# Plytka_AVR.net
KiCad netlist of a schematic drawn in EAGLE
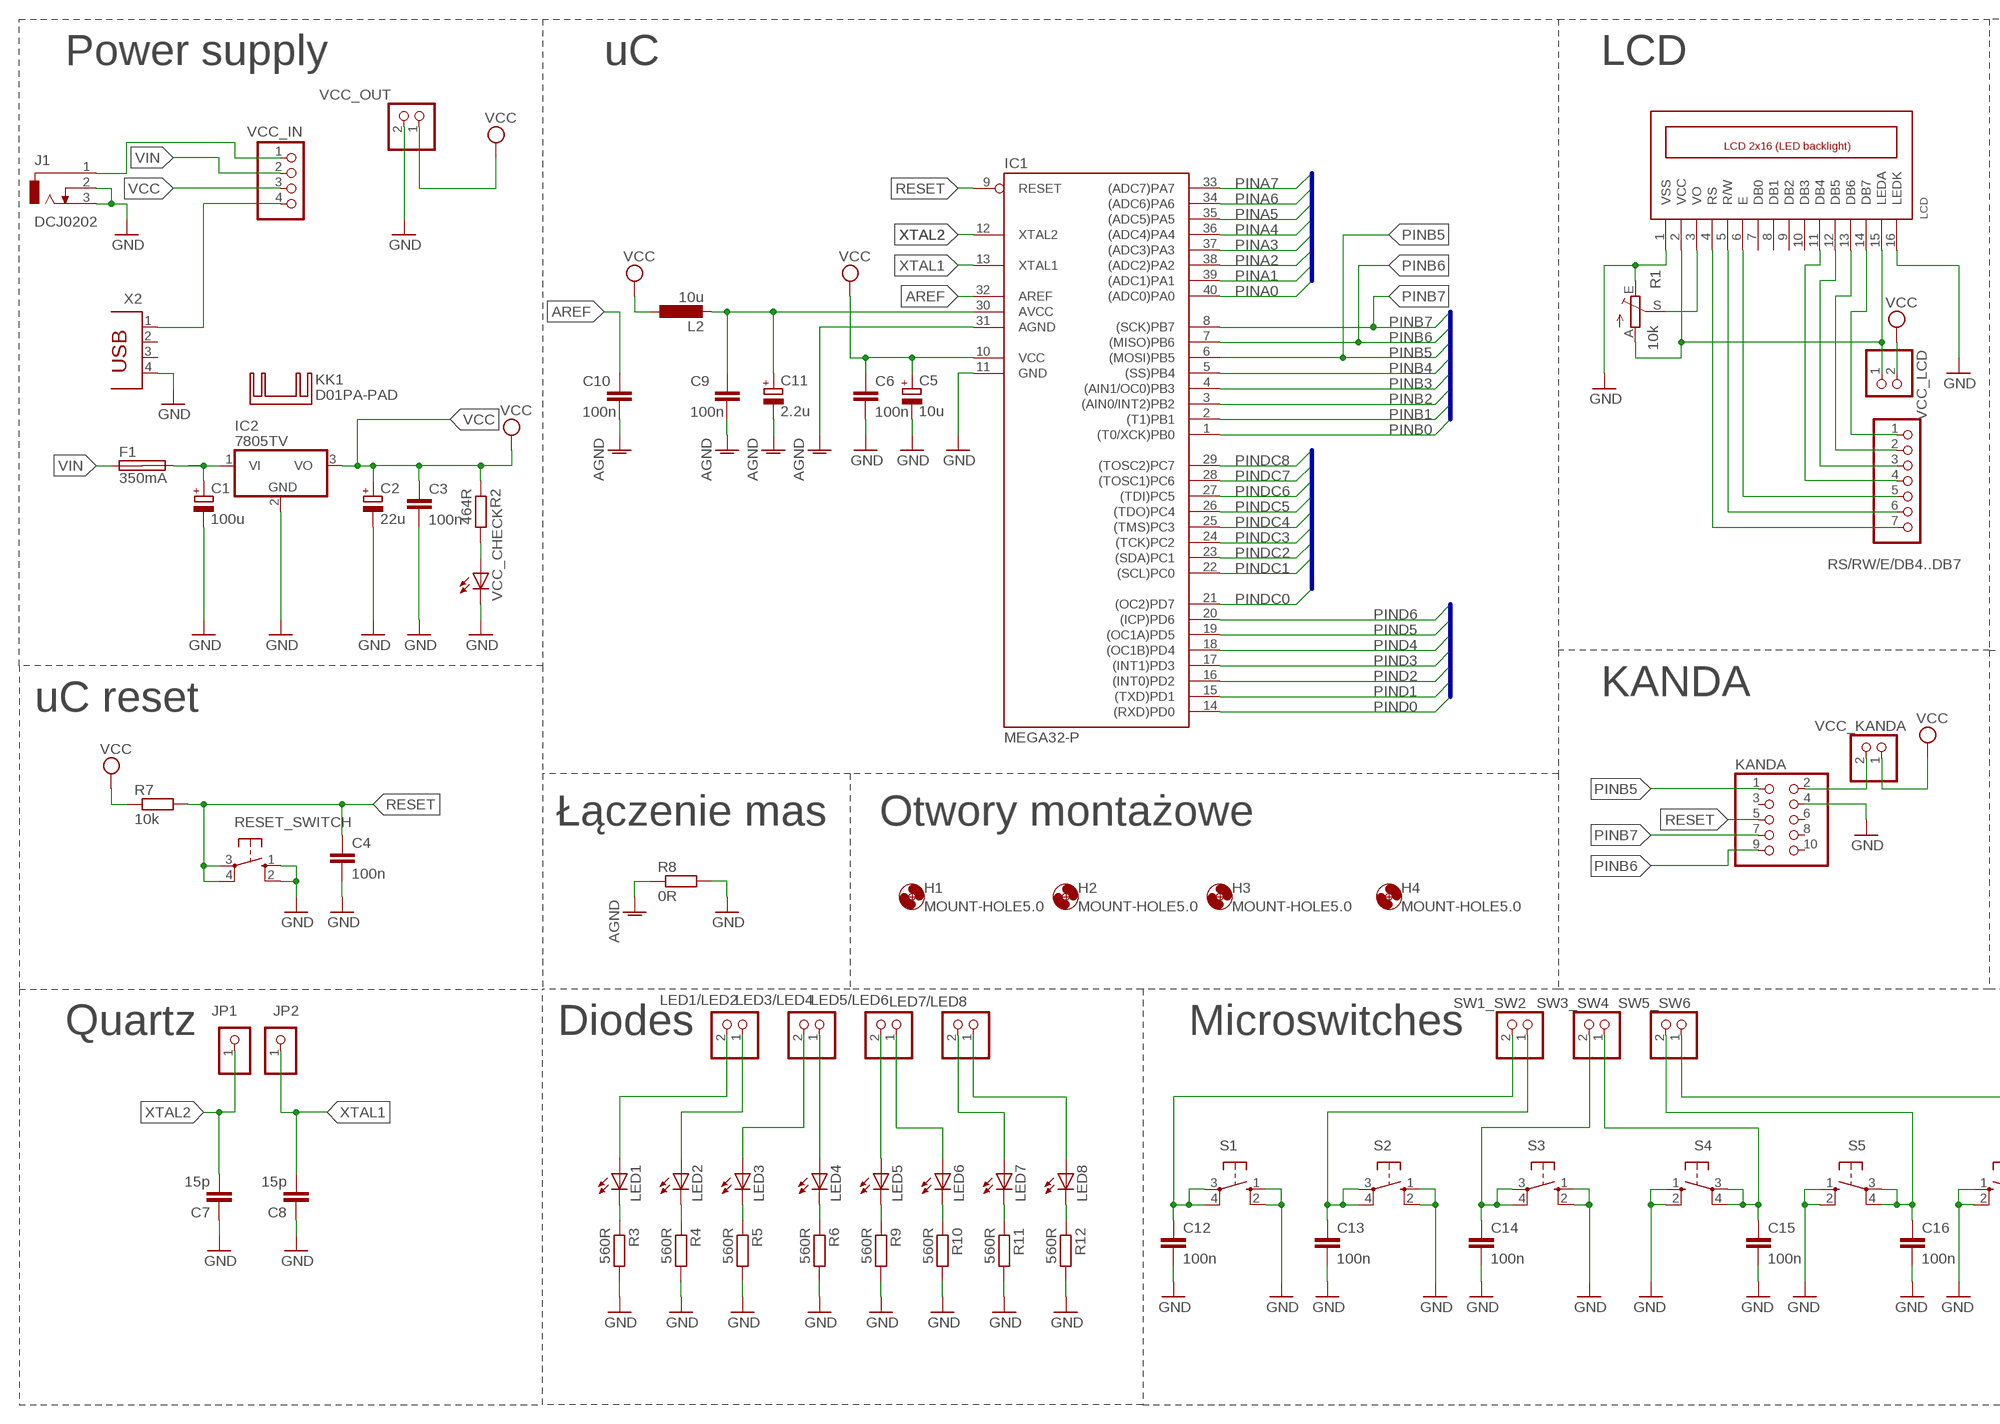
[diagram p0: schematic, sheet 1, part 1 of 2]
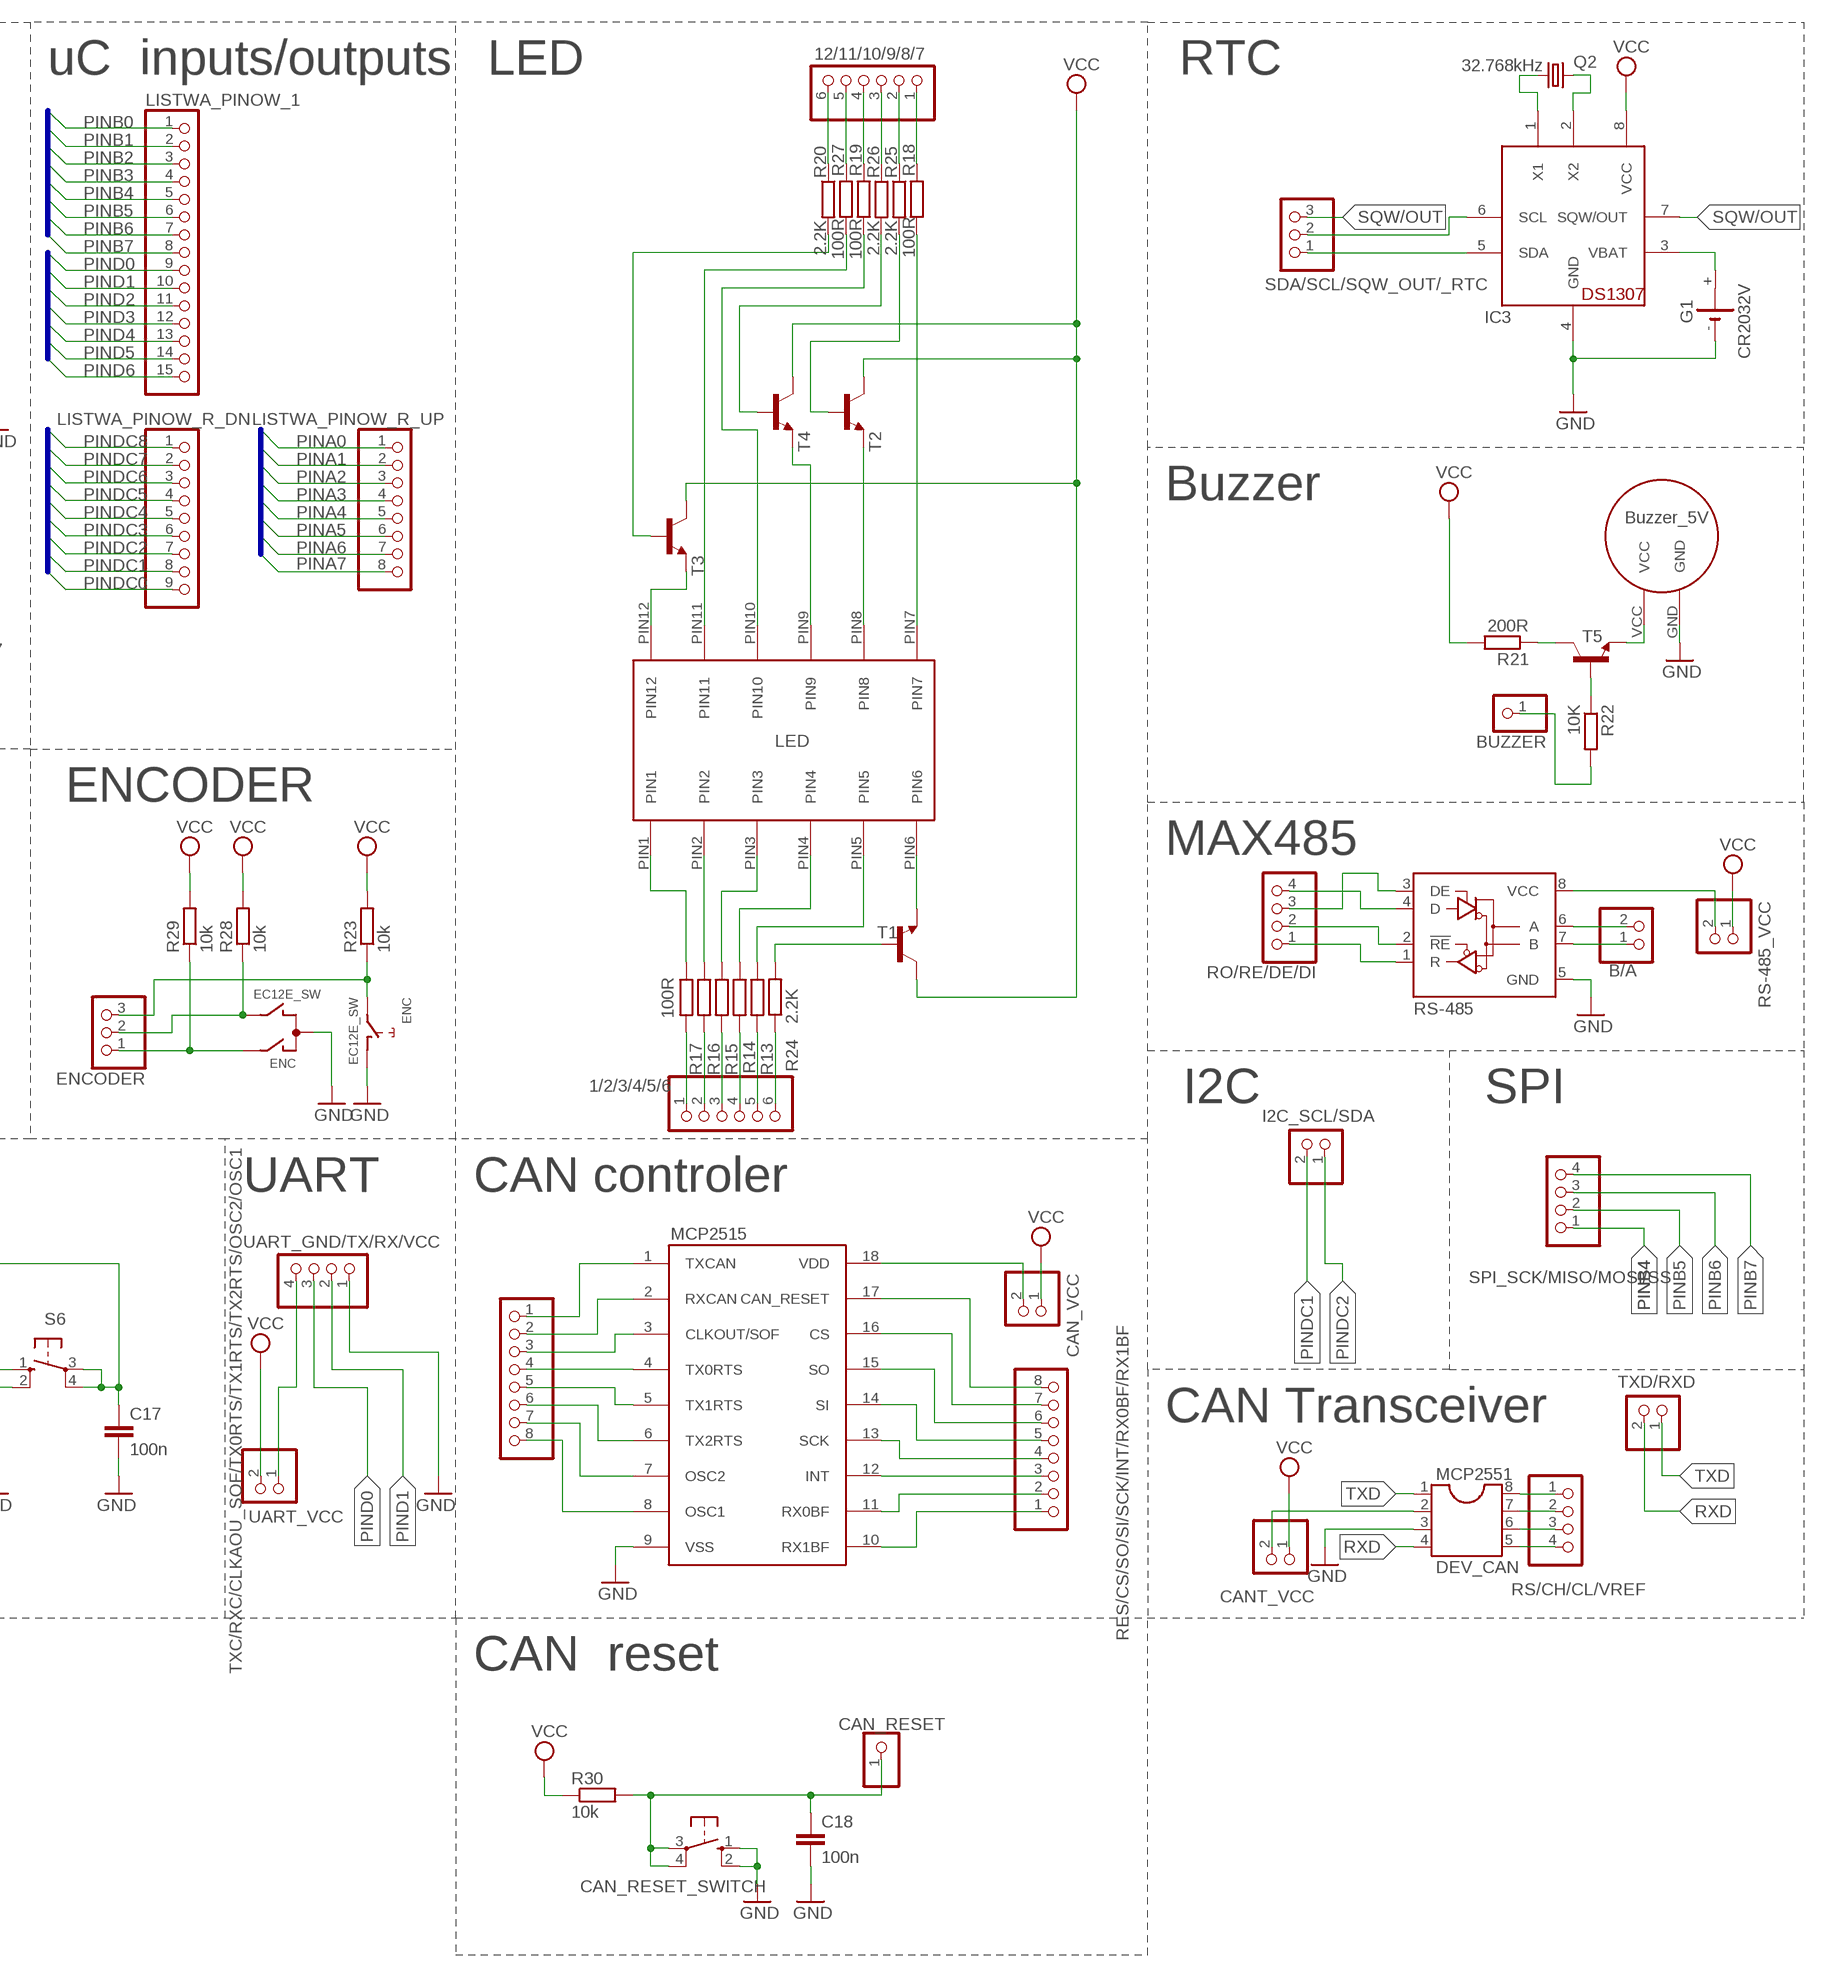
[diagram p1: schematic, sheet 1, part 2 of 2]

(export (version "E")
  (design (tool "Eeschema 10.0.6"))
  (components
    (comp (ref "1/2/3/4/5/6")
      (value "PINHD-1X6")
      (footprint "eagle-import:1X06")
      (libsource (lib "eagle-import") (part "PINHD-1X6"))
    )
    (comp (ref "12/11/10/9/8/7")
      (value "PINHD-1X6")
      (footprint "eagle-import:1X06")
      (libsource (lib "eagle-import") (part "PINHD-1X6"))
    )
    (comp (ref "B/A")
      (value "PINHD-1X2")
      (footprint "eagle-import:1X02")
      (libsource (lib "eagle-import") (part "PINHD-1X2"))
    )
    (comp (ref "BUZZER")
      (value "PINHD-1X1")
      (footprint "eagle-import:1X01")
      (libsource (lib "eagle-import") (part "PINHD-1X1"))
    )
    (comp (ref "C1")
      (value "100u")
      (footprint "eagle-import:E2,5-6")
      (libsource (lib "eagle-import") (part "CPOL-EUE2.5-6"))
    )
    (comp (ref "C2")
      (value "22u")
      (footprint "eagle-import:E2,5-6")
      (libsource (lib "eagle-import") (part "CPOL-EUE2.5-6"))
    )
    (comp (ref "C3")
      (value "100n")
      (footprint "eagle-import:C050-024X044")
      (libsource (lib "eagle-import") (part "C-EU050-024X044"))
    )
    (comp (ref "C4")
      (value "100n")
      (footprint "eagle-import:C050-024X044")
      (libsource (lib "eagle-import") (part "C-EU050-024X044"))
    )
    (comp (ref "C5")
      (value "10u")
      (footprint "eagle-import:E2,5-6")
      (libsource (lib "eagle-import") (part "CPOL-EUE2.5-6"))
    )
    (comp (ref "C6")
      (value "100n")
      (footprint "eagle-import:C050-024X044")
      (libsource (lib "eagle-import") (part "C-EU050-024X044"))
    )
    (comp (ref "C7")
      (value "15p")
      (footprint "eagle-import:C050-024X044")
      (libsource (lib "eagle-import") (part "C-EU050-024X044"))
    )
    (comp (ref "C8")
      (value "15p")
      (footprint "eagle-import:C050-024X044")
      (libsource (lib "eagle-import") (part "C-EU050-024X044"))
    )
    (comp (ref "C9")
      (value "100n")
      (footprint "eagle-import:C050-024X044")
      (libsource (lib "eagle-import") (part "C-EU050-024X044"))
    )
    (comp (ref "C10")
      (value "100n")
      (footprint "eagle-import:C050-024X044")
      (libsource (lib "eagle-import") (part "C-EU050-024X044"))
    )
    (comp (ref "C11")
      (value "2.2u")
      (footprint "eagle-import:E2,5-6")
      (libsource (lib "eagle-import") (part "CPOL-EUE2.5-6"))
    )
    (comp (ref "C12")
      (value "100n")
      (footprint "eagle-import:C050-024X044")
      (libsource (lib "eagle-import") (part "C-EU050-024X044"))
    )
    (comp (ref "C13")
      (value "100n")
      (footprint "eagle-import:C050-024X044")
      (libsource (lib "eagle-import") (part "C-EU050-024X044"))
    )
    (comp (ref "C14")
      (value "100n")
      (footprint "eagle-import:C050-024X044")
      (libsource (lib "eagle-import") (part "C-EU050-024X044"))
    )
    (comp (ref "C15")
      (value "100n")
      (footprint "eagle-import:C050-024X044")
      (libsource (lib "eagle-import") (part "C-EU050-024X044"))
    )
    (comp (ref "C16")
      (value "100n")
      (footprint "eagle-import:C050-024X044")
      (libsource (lib "eagle-import") (part "C-EU050-024X044"))
    )
    (comp (ref "C17")
      (value "100n")
      (footprint "eagle-import:C050-024X044")
      (libsource (lib "eagle-import") (part "C-EU050-024X044"))
    )
    (comp (ref "C18")
      (value "100n")
      (footprint "eagle-import:C050-024X044")
      (libsource (lib "eagle-import") (part "C-EU050-024X044"))
    )
    (comp (ref "CANT_VCC")
      (value "PINHD-1X2")
      (footprint "eagle-import:1X02")
      (libsource (lib "eagle-import") (part "PINHD-1X2"))
    )
    (comp (ref "CAN_RESET")
      (value "PINHD-1X1")
      (footprint "eagle-import:1X01")
      (libsource (lib "eagle-import") (part "PINHD-1X1"))
    )
    (comp (ref "CAN_RESET_SWITCH")
      (value "10-XX")
      (footprint "eagle-import:B3F-10XX")
      (fields (field (name "MPN") "B3F-1000"))
      (libsource (lib "eagle-import") (part "10-XX"))
    )
    (comp (ref "CAN_VCC")
      (value "PINHD-1X2")
      (footprint "eagle-import:1X02")
      (libsource (lib "eagle-import") (part "PINHD-1X2"))
    )
    (comp (ref "ENC")
      (value "EC12E_SW")
      (footprint "eagle-import:ALPS_EC12E_SW")
      (fields (field (name "MPN") "EC12E2424407"))
      (libsource (lib "eagle-import") (part "EC12E_SW"))
    )
    (comp (ref "ENCODER")
      (value "PINHD-1X3")
      (footprint "eagle-import:1X03")
      (libsource (lib "eagle-import") (part "PINHD-1X3"))
    )
    (comp (ref "F1")
      (value "350mA")
      (footprint "eagle-import:SHK20L")
      (libsource (lib "eagle-import") (part "SHK20L"))
    )
    (comp (ref "G1")
      (value "CR2032V")
      (footprint "eagle-import:CR2032V")
      (libsource (lib "eagle-import") (part "CR2032V"))
    )
    (comp (ref "H1")
      (value "MOUNT-HOLE5.0")
      (footprint "eagle-import:5,0")
      (libsource (lib "eagle-import") (part "MOUNT-HOLE5.0"))
    )
    (comp (ref "H2")
      (value "MOUNT-HOLE5.0")
      (footprint "eagle-import:5,0")
      (libsource (lib "eagle-import") (part "MOUNT-HOLE5.0"))
    )
    (comp (ref "H3")
      (value "MOUNT-HOLE5.0")
      (footprint "eagle-import:5,0")
      (libsource (lib "eagle-import") (part "MOUNT-HOLE5.0"))
    )
    (comp (ref "H4")
      (value "MOUNT-HOLE5.0")
      (footprint "eagle-import:5,0")
      (libsource (lib "eagle-import") (part "MOUNT-HOLE5.0"))
    )
    (comp (ref "I2C_SCL/SDA")
      (value "PINHD-1X2")
      (footprint "eagle-import:1X02")
      (libsource (lib "eagle-import") (part "PINHD-1X2"))
    )
    (comp (ref "IC1")
      (value "MEGA32-P")
      (footprint "eagle-import:DIL40")
      (fields (field (name "MPN") "ATMEGA32-16PU"))
      (libsource (lib "eagle-import") (part "MEGA32-P"))
    )
    (comp (ref "IC2")
      (value "7805TV")
      (footprint "eagle-import:TO220V")
      (libsource (lib "eagle-import") (part "78TV05"))
    )
    (comp (ref "IC3")
      (value "DS1307")
      (footprint "eagle-import:DIL08")
      (libsource (lib "eagle-import") (part "DS1307"))
    )
    (comp (ref "J1")
      (value "DCJ0202")
      (footprint "eagle-import:DCJ0202")
      (libsource (lib "eagle-import") (part "DCJ0202"))
    )
    (comp (ref "JP1")
      (value "PINHD-1X1")
      (footprint "eagle-import:1X01")
      (libsource (lib "eagle-import") (part "PINHD-1X1"))
    )
    (comp (ref "JP2")
      (value "PINHD-1X1")
      (footprint "eagle-import:1X01")
      (libsource (lib "eagle-import") (part "PINHD-1X1"))
    )
    (comp (ref "KANDA")
      (value "PINHD-2X5")
      (footprint "eagle-import:2X05")
      (libsource (lib "eagle-import") (part "PINHD-2X5"))
    )
    (comp (ref "KK1")
      (value "D01PA-PAD")
      (footprint "eagle-import:D01PA-PAD")
      (libsource (lib "eagle-import") (part "D01PA-PAD"))
    )
    (comp (ref "L2")
      (value "10u")
      (footprint "eagle-import:0204_7")
      (libsource (lib "eagle-import") (part "L-EU0204/7"))
    )
    (comp (ref "LCD")
      (value "LCD_2X16_SIL")
      (footprint "eagle-import:HY-1602F")
      (libsource (lib "eagle-import") (part "LCD_2X16_SIL"))
    )
    (comp (ref "LED1")
      (value "LED5MM")
      (footprint "eagle-import:LED5MM")
      (libsource (lib "eagle-import") (part "LED5MM"))
    )
    (comp (ref "LED1/LED2")
      (value "PINHD-1X2")
      (footprint "eagle-import:1X02")
      (libsource (lib "eagle-import") (part "PINHD-1X2"))
    )
    (comp (ref "LED2")
      (value "LED5MM")
      (footprint "eagle-import:LED5MM")
      (libsource (lib "eagle-import") (part "LED5MM"))
    )
    (comp (ref "LED3")
      (value "LED5MM")
      (footprint "eagle-import:LED5MM")
      (libsource (lib "eagle-import") (part "LED5MM"))
    )
    (comp (ref "LED3/LED4")
      (value "PINHD-1X2")
      (footprint "eagle-import:1X02")
      (libsource (lib "eagle-import") (part "PINHD-1X2"))
    )
    (comp (ref "LED4")
      (value "LED5MM")
      (footprint "eagle-import:LED5MM")
      (libsource (lib "eagle-import") (part "LED5MM"))
    )
    (comp (ref "LED5")
      (value "LED5MM")
      (footprint "eagle-import:LED5MM")
      (libsource (lib "eagle-import") (part "LED5MM"))
    )
    (comp (ref "LED5/LED6")
      (value "PINHD-1X2")
      (footprint "eagle-import:1X02")
      (libsource (lib "eagle-import") (part "PINHD-1X2"))
    )
    (comp (ref "LED6")
      (value "LED5MM")
      (footprint "eagle-import:LED5MM")
      (libsource (lib "eagle-import") (part "LED5MM"))
    )
    (comp (ref "LED7")
      (value "LED5MM")
      (footprint "eagle-import:LED5MM")
      (libsource (lib "eagle-import") (part "LED5MM"))
    )
    (comp (ref "LED7/LED8")
      (value "PINHD-1X2")
      (footprint "eagle-import:1X02")
      (libsource (lib "eagle-import") (part "PINHD-1X2"))
    )
    (comp (ref "LED8")
      (value "LED5MM")
      (footprint "eagle-import:LED5MM")
      (libsource (lib "eagle-import") (part "LED5MM"))
    )
    (comp (ref "LISTWA_PINOW_1")
      (value "PINHD-1X15")
      (footprint "eagle-import:1X15")
      (libsource (lib "eagle-import") (part "PINHD-1X15"))
    )
    (comp (ref "LISTWA_PINOW_R_DN")
      (value "PINHD-1X9")
      (footprint "eagle-import:1X09")
      (libsource (lib "eagle-import") (part "PINHD-1X9"))
    )
    (comp (ref "LISTWA_PINOW_R_UP")
      (value "PINHD-1X8MAT8")
      (footprint "eagle-import:1X08")
      (libsource (lib "eagle-import") (part "PINHD-1X8MAT8"))
    )
    (comp (ref "MCP2551")
      (value "DEV_CAN")
      (footprint "eagle-import:DIL08")
      (libsource (lib "eagle-import") (part "DEV_CAN"))
    )
    (comp (ref "Q2")
      (value "32.768kHz")
      (footprint "eagle-import:TC26V")
      (libsource (lib "eagle-import") (part "CRYSTALTC26V"))
    )
    (comp (ref "R1")
      (value "10k")
      (footprint "eagle-import:CA6V")
      (libsource (lib "eagle-import") (part "TRIM_EU-CA6V"))
    )
    (comp (ref "R2")
      (value "464R")
      (footprint "eagle-import:0204_7")
      (libsource (lib "eagle-import") (part "R-EU_0204/7"))
    )
    (comp (ref "R3")
      (value "560R")
      (footprint "eagle-import:0204_7")
      (libsource (lib "eagle-import") (part "R-EU_0204/7"))
    )
    (comp (ref "R4")
      (value "560R")
      (footprint "eagle-import:0204_7")
      (libsource (lib "eagle-import") (part "R-EU_0204/7"))
    )
    (comp (ref "R5")
      (value "560R")
      (footprint "eagle-import:0204_7")
      (libsource (lib "eagle-import") (part "R-EU_0204/7"))
    )
    (comp (ref "R6")
      (value "560R")
      (footprint "eagle-import:0204_7")
      (libsource (lib "eagle-import") (part "R-EU_0204/7"))
    )
    (comp (ref "R7")
      (value "10k")
      (footprint "eagle-import:0204_7")
      (libsource (lib "eagle-import") (part "R-EU_0204/7"))
    )
    (comp (ref "R8")
      (value "0R")
      (footprint "eagle-import:0204_7")
      (libsource (lib "eagle-import") (part "R-EU_0204/7"))
    )
    (comp (ref "R9")
      (value "560R")
      (footprint "eagle-import:0204_7")
      (libsource (lib "eagle-import") (part "R-EU_0204/7"))
    )
    (comp (ref "R10")
      (value "560R")
      (footprint "eagle-import:0204_7")
      (libsource (lib "eagle-import") (part "R-EU_0204/7"))
    )
    (comp (ref "R11")
      (value "560R")
      (footprint "eagle-import:0204_7")
      (libsource (lib "eagle-import") (part "R-EU_0204/7"))
    )
    (comp (ref "R12")
      (value "560R")
      (footprint "eagle-import:0204_7")
      (libsource (lib "eagle-import") (part "R-EU_0204/7"))
    )
    (comp (ref "R13")
      (value "100R")
      (footprint "eagle-import:0204_7")
      (libsource (lib "eagle-import") (part "R-EU_0204/7"))
    )
    (comp (ref "R14")
      (value "100R")
      (footprint "eagle-import:0204_7")
      (libsource (lib "eagle-import") (part "R-EU_0204/7"))
    )
    (comp (ref "R15")
      (value "100R")
      (footprint "eagle-import:0204_7")
      (libsource (lib "eagle-import") (part "R-EU_0204/7"))
    )
    (comp (ref "R16")
      (value "100R")
      (footprint "eagle-import:0204_7")
      (libsource (lib "eagle-import") (part "R-EU_0204/7"))
    )
    (comp (ref "R17")
      (value "100R")
      (footprint "eagle-import:0204_7")
      (libsource (lib "eagle-import") (part "R-EU_0204/7"))
    )
    (comp (ref "R18")
      (value "100R")
      (footprint "eagle-import:0204_7")
      (libsource (lib "eagle-import") (part "R-EU_0204/7"))
    )
    (comp (ref "R19")
      (value "100R")
      (footprint "eagle-import:0204_7")
      (libsource (lib "eagle-import") (part "R-EU_0204/7"))
    )
    (comp (ref "R20")
      (value "2.2K")
      (footprint "eagle-import:0204_7")
      (libsource (lib "eagle-import") (part "R-EU_0204/7"))
    )
    (comp (ref "R21")
      (value "200R")
      (footprint "eagle-import:0204_7")
      (libsource (lib "eagle-import") (part "R-EU_0204/7"))
    )
    (comp (ref "R22")
      (value "10K")
      (footprint "eagle-import:0204_7")
      (libsource (lib "eagle-import") (part "R-EU_0204/7"))
    )
    (comp (ref "R23")
      (value "10k")
      (footprint "eagle-import:0204_7")
      (libsource (lib "eagle-import") (part "R-EU_0204/7"))
    )
    (comp (ref "R24")
      (value "2.2K")
      (footprint "eagle-import:0204_7")
      (libsource (lib "eagle-import") (part "R-EU_0204/7"))
    )
    (comp (ref "R25")
      (value "2.2K")
      (footprint "eagle-import:0204_7")
      (libsource (lib "eagle-import") (part "R-EU_0204/7"))
    )
    (comp (ref "R26")
      (value "2.2K")
      (footprint "eagle-import:0204_7")
      (libsource (lib "eagle-import") (part "R-EU_0204/7"))
    )
    (comp (ref "R27")
      (value "100R")
      (footprint "eagle-import:0204_7")
      (libsource (lib "eagle-import") (part "R-EU_0204/7"))
    )
    (comp (ref "R28")
      (value "10k")
      (footprint "eagle-import:0204_7")
      (libsource (lib "eagle-import") (part "R-EU_0204/7"))
    )
    (comp (ref "R29")
      (value "10k")
      (footprint "eagle-import:0204_7")
      (libsource (lib "eagle-import") (part "R-EU_0204/7"))
    )
    (comp (ref "R30")
      (value "10k")
      (footprint "eagle-import:0204_7")
      (libsource (lib "eagle-import") (part "R-EU_0204/7"))
    )
    (comp (ref "RES/CS/SO/SI/SCK/INT/RX0BF/RX1BF")
      (value "PINHD-1X8")
      (footprint "eagle-import:1X08")
      (libsource (lib "eagle-import") (part "PINHD-1X8"))
    )
    (comp (ref "RESET_SWITCH")
      (value "10-XX")
      (footprint "eagle-import:B3F-10XX")
      (fields (field (name "MPN") "B3F-1000"))
      (libsource (lib "eagle-import") (part "10-XX"))
    )
    (comp (ref "RO/RE/DE/DI")
      (value "PINHD-1X4")
      (footprint "eagle-import:1X04")
      (libsource (lib "eagle-import") (part "PINHD-1X4"))
    )
    (comp (ref "RS-485")
      (value "RS-485")
      (footprint "eagle-import:DIL08")
      (libsource (lib "eagle-import") (part "75176AP"))
    )
    (comp (ref "RS-485_VCC")
      (value "PINHD-1X2")
      (footprint "eagle-import:1X02")
      (libsource (lib "eagle-import") (part "PINHD-1X2"))
    )
    (comp (ref "RS/CH/CL/VREF")
      (value "PINHD-1X4")
      (footprint "eagle-import:1X04")
      (libsource (lib "eagle-import") (part "PINHD-1X4"))
    )
    (comp (ref "RS/RW/E/DB4..DB7")
      (value "PINHD-1X7MAT_LCD")
      (footprint "eagle-import:1X07")
      (libsource (lib "eagle-import") (part "PINHD-1X7MAT_LCD"))
    )
    (comp (ref "S1")
      (value "10-XX")
      (footprint "eagle-import:B3F-10XX")
      (fields (field (name "MPN") "B3F-1000"))
      (libsource (lib "eagle-import") (part "10-XX"))
    )
    (comp (ref "S2")
      (value "10-XX")
      (footprint "eagle-import:B3F-10XX")
      (fields (field (name "MPN") "B3F-1000"))
      (libsource (lib "eagle-import") (part "10-XX"))
    )
    (comp (ref "S3")
      (value "10-XX")
      (footprint "eagle-import:B3F-10XX")
      (fields (field (name "MPN") "B3F-1000"))
      (libsource (lib "eagle-import") (part "10-XX"))
    )
    (comp (ref "S4")
      (value "10-XX")
      (footprint "eagle-import:B3F-10XX")
      (fields (field (name "MPN") "B3F-1000"))
      (libsource (lib "eagle-import") (part "10-XX"))
    )
    (comp (ref "S5")
      (value "10-XX")
      (footprint "eagle-import:B3F-10XX")
      (fields (field (name "MPN") "B3F-1000"))
      (libsource (lib "eagle-import") (part "10-XX"))
    )
    (comp (ref "S6")
      (value "10-XX")
      (footprint "eagle-import:B3F-10XX")
      (fields (field (name "MPN") "B3F-1000"))
      (libsource (lib "eagle-import") (part "10-XX"))
    )
    (comp (ref "SDA/SCL/SQW_OUT/_RTC")
      (value "PINHD-1X3")
      (footprint "eagle-import:1X03")
      (libsource (lib "eagle-import") (part "PINHD-1X3"))
    )
    (comp (ref "SPI_SCK/MISO/MOSI/SS")
      (value "PINHD-1X4")
      (footprint "eagle-import:1X04")
      (libsource (lib "eagle-import") (part "PINHD-1X4"))
    )
    (comp (ref "SW1_SW2")
      (value "PINHD-1X2")
      (footprint "eagle-import:1X02")
      (libsource (lib "eagle-import") (part "PINHD-1X2"))
    )
    (comp (ref "SW3_SW4")
      (value "PINHD-1X2")
      (footprint "eagle-import:1X02")
      (libsource (lib "eagle-import") (part "PINHD-1X2"))
    )
    (comp (ref "SW5_SW6")
      (value "PINHD-1X2")
      (footprint "eagle-import:1X02")
      (libsource (lib "eagle-import") (part "PINHD-1X2"))
    )
    (comp (ref "T1")
      (value "-NPN-TO92")
      (footprint "eagle-import:TO92")
      (libsource (lib "eagle-import") (part "-NPN-TO92"))
    )
    (comp (ref "T2")
      (value "-NPN-TO92")
      (footprint "eagle-import:TO92")
      (libsource (lib "eagle-import") (part "-NPN-TO92"))
    )
    (comp (ref "T3")
      (value "-NPN-TO92")
      (footprint "eagle-import:TO92")
      (libsource (lib "eagle-import") (part "-NPN-TO92"))
    )
    (comp (ref "T4")
      (value "-NPN-TO92")
      (footprint "eagle-import:TO92")
      (libsource (lib "eagle-import") (part "-NPN-TO92"))
    )
    (comp (ref "T5")
      (value "-NPN-TO92")
      (footprint "eagle-import:TO92")
      (libsource (lib "eagle-import") (part "-NPN-TO92"))
    )
    (comp (ref "TXC/RXC/CLKAOU_SOF/TX0RTS/TX1RTS/TX2RTS/OSC2/OSC1")
      (value "PINHD-1X8")
      (footprint "eagle-import:1X08")
      (libsource (lib "eagle-import") (part "PINHD-1X8"))
    )
    (comp (ref "TXD/RXD")
      (value "PINHD-1X2")
      (footprint "eagle-import:1X02")
      (libsource (lib "eagle-import") (part "PINHD-1X2"))
    )
    (comp (ref "U$1")
      (value "LED_MAT")
      (footprint "eagle-import:LED_MOJ")
      (libsource (lib "eagle-import") (part "LED_MAT"))
    )
    (comp (ref "U$2")
      (value "BUZZER_MAT")
      (footprint "eagle-import:BUZZER_MAT")
      (libsource (lib "eagle-import") (part "BUZZER_MAT"))
    )
    (comp (ref "U$3")
      (value "MCP2515")
      (footprint "eagle-import:DIP18")
      (libsource (lib "eagle-import") (part "MCP2515"))
    )
    (comp (ref "UART_GND/TX/RX/VCC")
      (value "PINHD-1X4")
      (footprint "eagle-import:1X04")
      (libsource (lib "eagle-import") (part "PINHD-1X4"))
    )
    (comp (ref "UART_VCC")
      (value "PINHD-1X2")
      (footprint "eagle-import:1X02")
      (libsource (lib "eagle-import") (part "PINHD-1X2"))
    )
    (comp (ref "VCC_CHECK")
      (value "LED5MM")
      (footprint "eagle-import:LED5MM")
      (libsource (lib "eagle-import") (part "LED5MM"))
    )
    (comp (ref "VCC_IN")
      (value "PINHD-1X4")
      (footprint "eagle-import:1X04")
      (libsource (lib "eagle-import") (part "PINHD-1X4"))
    )
    (comp (ref "VCC_KANDA")
      (value "PINHD-1X2")
      (footprint "eagle-import:1X02")
      (libsource (lib "eagle-import") (part "PINHD-1X2"))
    )
    (comp (ref "VCC_LCD")
      (value "PINHD-1X2")
      (footprint "eagle-import:1X02")
      (libsource (lib "eagle-import") (part "PINHD-1X2"))
    )
    (comp (ref "VCC_OUT")
      (value "PINHD-1X2")
      (footprint "eagle-import:1X02")
      (libsource (lib "eagle-import") (part "PINHD-1X2"))
    )
    (comp (ref "X2")
      (value "PN87520")
      (footprint "eagle-import:PN87520")
      (libsource (lib "eagle-import") (part "PN87520"))
    )
  )
  (nets
    (net (code "1") (name "/PINA0") (class "Default")
      (node (ref "IC1") (pin "40") (pinfunction "(ADC0)PA0_40") (pintype "bidirectional"))
      (node (ref "LISTWA_PINOW_R_UP") (pin "1") (pinfunction "1_1") (pintype "passive"))
    )
    (net (code "2") (name "/PINA1") (class "Default")
      (node (ref "IC1") (pin "39") (pinfunction "(ADC1)PA1_39") (pintype "bidirectional"))
      (node (ref "LISTWA_PINOW_R_UP") (pin "2") (pinfunction "2_2") (pintype "passive"))
    )
    (net (code "3") (name "/PINA2") (class "Default")
      (node (ref "IC1") (pin "38") (pinfunction "(ADC2)PA2_38") (pintype "bidirectional"))
      (node (ref "LISTWA_PINOW_R_UP") (pin "3") (pinfunction "3_3") (pintype "passive"))
    )
    (net (code "4") (name "/PINA3") (class "Default")
      (node (ref "IC1") (pin "37") (pinfunction "(ADC3)PA3_37") (pintype "bidirectional"))
      (node (ref "LISTWA_PINOW_R_UP") (pin "4") (pinfunction "4_4") (pintype "passive"))
    )
    (net (code "5") (name "/PINA4") (class "Default")
      (node (ref "IC1") (pin "36") (pinfunction "(ADC4)PA4_36") (pintype "bidirectional"))
      (node (ref "LISTWA_PINOW_R_UP") (pin "5") (pinfunction "5_5") (pintype "passive"))
    )
    (net (code "6") (name "/PINA5") (class "Default")
      (node (ref "IC1") (pin "35") (pinfunction "(ADC5)PA5_35") (pintype "bidirectional"))
      (node (ref "LISTWA_PINOW_R_UP") (pin "6") (pinfunction "6_6") (pintype "passive"))
    )
    (net (code "7") (name "/PINA6") (class "Default")
      (node (ref "IC1") (pin "34") (pinfunction "(ADC6)PA6_34") (pintype "bidirectional"))
      (node (ref "LISTWA_PINOW_R_UP") (pin "7") (pinfunction "7_7") (pintype "passive"))
    )
    (net (code "8") (name "/PINA7") (class "Default")
      (node (ref "IC1") (pin "33") (pinfunction "(ADC7)PA7_33") (pintype "bidirectional"))
      (node (ref "LISTWA_PINOW_R_UP") (pin "8") (pinfunction "8_8") (pintype "passive"))
    )
    (net (code "9") (name "/PINB0") (class "Default")
      (node (ref "IC1") (pin "1") (pinfunction "(T0/XCK)PB0_1") (pintype "bidirectional"))
      (node (ref "LISTWA_PINOW_1") (pin "1") (pinfunction "1_1") (pintype "passive"))
    )
    (net (code "10") (name "/PINB1") (class "Default")
      (node (ref "IC1") (pin "2") (pinfunction "(T1)PB1_2") (pintype "bidirectional"))
      (node (ref "LISTWA_PINOW_1") (pin "2") (pinfunction "2_2") (pintype "passive"))
    )
    (net (code "11") (name "/PINB2") (class "Default")
      (node (ref "IC1") (pin "3") (pinfunction "(AIN0/INT2)PB2_3") (pintype "bidirectional"))
      (node (ref "LISTWA_PINOW_1") (pin "3") (pinfunction "3_3") (pintype "passive"))
    )
    (net (code "12") (name "/PINB3") (class "Default")
      (node (ref "IC1") (pin "4") (pinfunction "(AIN1/OC0)PB3_4") (pintype "bidirectional"))
      (node (ref "LISTWA_PINOW_1") (pin "4") (pinfunction "4_4") (pintype "passive"))
    )
    (net (code "13") (name "/PIND2") (class "Default")
      (node (ref "IC1") (pin "16") (pinfunction "(INT0)PD2_16") (pintype "bidirectional"))
      (node (ref "LISTWA_PINOW_1") (pin "11") (pinfunction "11_11") (pintype "passive"))
    )
    (net (code "14") (name "/PIND3") (class "Default")
      (node (ref "IC1") (pin "17") (pinfunction "(INT1)PD3_17") (pintype "bidirectional"))
      (node (ref "LISTWA_PINOW_1") (pin "12") (pinfunction "12_12") (pintype "passive"))
    )
    (net (code "15") (name "/PIND4") (class "Default")
      (node (ref "IC1") (pin "18") (pinfunction "(OC1B)PD4_18") (pintype "bidirectional"))
      (node (ref "LISTWA_PINOW_1") (pin "13") (pinfunction "13_13") (pintype "passive"))
    )
    (net (code "16") (name "/PIND5") (class "Default")
      (node (ref "IC1") (pin "19") (pinfunction "(OC1A)PD5_19") (pintype "bidirectional"))
      (node (ref "LISTWA_PINOW_1") (pin "14") (pinfunction "14_14") (pintype "passive"))
    )
    (net (code "17") (name "/PIND6") (class "Default")
      (node (ref "IC1") (pin "20") (pinfunction "(ICP)PD6_20") (pintype "bidirectional"))
      (node (ref "LISTWA_PINOW_1") (pin "15") (pinfunction "15_15") (pintype "passive"))
    )
    (net (code "18") (name "/PINDC0") (class "Default")
      (node (ref "IC1") (pin "21") (pinfunction "(OC2)PD7_21") (pintype "bidirectional"))
      (node (ref "LISTWA_PINOW_R_DN") (pin "9") (pinfunction "9_9") (pintype "passive"))
    )
    (net (code "19") (name "/PINDC3") (class "Default")
      (node (ref "IC1") (pin "24") (pinfunction "(TCK)PC2_24") (pintype "bidirectional"))
      (node (ref "LISTWA_PINOW_R_DN") (pin "6") (pinfunction "6_6") (pintype "passive"))
    )
    (net (code "20") (name "/PINDC4") (class "Default")
      (node (ref "IC1") (pin "25") (pinfunction "(TMS)PC3_25") (pintype "bidirectional"))
      (node (ref "LISTWA_PINOW_R_DN") (pin "5") (pinfunction "5_5") (pintype "passive"))
    )
    (net (code "21") (name "/PINDC5") (class "Default")
      (node (ref "IC1") (pin "26") (pinfunction "(TDO)PC4_26") (pintype "bidirectional"))
      (node (ref "LISTWA_PINOW_R_DN") (pin "4") (pinfunction "4_4") (pintype "passive"))
    )
    (net (code "22") (name "/PINDC6") (class "Default")
      (node (ref "IC1") (pin "27") (pinfunction "(TDI)PC5_27") (pintype "bidirectional"))
      (node (ref "LISTWA_PINOW_R_DN") (pin "3") (pinfunction "3_3") (pintype "passive"))
    )
    (net (code "23") (name "/PINDC7") (class "Default")
      (node (ref "IC1") (pin "28") (pinfunction "(TOSC1)PC6_28") (pintype "bidirectional"))
      (node (ref "LISTWA_PINOW_R_DN") (pin "2") (pinfunction "2_2") (pintype "passive"))
    )
    (net (code "24") (name "/PINDC8") (class "Default")
      (node (ref "IC1") (pin "29") (pinfunction "(TOSC2)PC7_29") (pintype "bidirectional"))
      (node (ref "LISTWA_PINOW_R_DN") (pin "1") (pinfunction "1_1") (pintype "passive"))
    )
    (net (code "25") (name "AGND") (class "Default")
      (node (ref "C10") (pin "2") (pinfunction "2_2") (pintype "passive"))
      (node (ref "C11") (pin "-") (pinfunction "-_-") (pintype "passive"))
      (node (ref "C9") (pin "2") (pinfunction "2_2") (pintype "passive"))
      (node (ref "IC1") (pin "31") (pinfunction "AGND_31") (pintype "power_in"))
      (node (ref "R8") (pin "1") (pinfunction "1_1") (pintype "passive"))
    )
    (net (code "26") (name "AREF") (class "Default")
      (node (ref "C10") (pin "1") (pinfunction "1_1") (pintype "passive"))
      (node (ref "IC1") (pin "32") (pinfunction "AREF_32") (pintype "passive"))
    )
    (net (code "27") (name "GND") (class "Default")
      (node (ref "C1") (pin "-") (pinfunction "-_-") (pintype "passive"))
      (node (ref "C12") (pin "2") (pinfunction "2_2") (pintype "passive"))
      (node (ref "C13") (pin "2") (pinfunction "2_2") (pintype "passive"))
      (node (ref "C14") (pin "2") (pinfunction "2_2") (pintype "passive"))
      (node (ref "C15") (pin "2") (pinfunction "2_2") (pintype "passive"))
      (node (ref "C16") (pin "2") (pinfunction "2_2") (pintype "passive"))
      (node (ref "C17") (pin "2") (pinfunction "2_2") (pintype "passive"))
      (node (ref "C18") (pin "2") (pinfunction "2_2") (pintype "passive"))
      (node (ref "C2") (pin "-") (pinfunction "-_-") (pintype "passive"))
      (node (ref "C3") (pin "2") (pinfunction "2_2") (pintype "passive"))
      (node (ref "C4") (pin "2") (pinfunction "2_2") (pintype "passive"))
      (node (ref "C5") (pin "-") (pinfunction "-_-") (pintype "passive"))
      (node (ref "C6") (pin "2") (pinfunction "2_2") (pintype "passive"))
      (node (ref "C7") (pin "1") (pinfunction "1_1") (pintype "passive"))
      (node (ref "C8") (pin "1") (pinfunction "1_1") (pintype "passive"))
      (node (ref "CAN_RESET_SWITCH") (pin "1") (pinfunction "S_1") (pintype "passive"))
      (node (ref "CAN_RESET_SWITCH") (pin "2") (pinfunction "S1_2") (pintype "passive"))
      (node (ref "ENC") (pin "C") (pinfunction "C_C") (pintype "passive"))
      (node (ref "ENC") (pin "D") (pinfunction "1_D") (pintype "passive"))
      (node (ref "G1") (pin "-") (pinfunction "-_-") (pintype "passive"))
      (node (ref "IC1") (pin "11") (pinfunction "GND_11") (pintype "power_in"))
      (node (ref "IC2") (pin "2") (pinfunction "GND_2") (pintype "passive"))
      (node (ref "IC3") (pin "4") (pinfunction "GND_4") (pintype "power_in"))
      (node (ref "J1") (pin "2") (pinfunction "2_2") (pintype "passive"))
      (node (ref "J1") (pin "3") (pinfunction "3_3") (pintype "passive"))
      (node (ref "KANDA") (pin "4") (pinfunction "4_4") (pintype "passive"))
      (node (ref "LCD") (pin "1") (pinfunction "VSS_1") (pintype "power_in"))
      (node (ref "LCD") (pin "16") (pinfunction "LEDK_16") (pintype "passive"))
      (node (ref "MCP2551") (pin "3") (pinfunction "VDD_3") (pintype "passive"))
      (node (ref "R1") (pin "E") (pinfunction "E_E") (pintype "passive"))
      (node (ref "R10") (pin "2") (pinfunction "2_2") (pintype "passive"))
      (node (ref "R11") (pin "2") (pinfunction "2_2") (pintype "passive"))
      (node (ref "R12") (pin "2") (pinfunction "2_2") (pintype "passive"))
      (node (ref "R3") (pin "2") (pinfunction "2_2") (pintype "passive"))
      (node (ref "R4") (pin "2") (pinfunction "2_2") (pintype "passive"))
      (node (ref "R5") (pin "2") (pinfunction "2_2") (pintype "passive"))
      (node (ref "R6") (pin "2") (pinfunction "2_2") (pintype "passive"))
      (node (ref "R8") (pin "2") (pinfunction "2_2") (pintype "passive"))
      (node (ref "R9") (pin "2") (pinfunction "2_2") (pintype "passive"))
      (node (ref "RESET_SWITCH") (pin "1") (pinfunction "S_1") (pintype "passive"))
      (node (ref "RESET_SWITCH") (pin "2") (pinfunction "S1_2") (pintype "passive"))
      (node (ref "RS-485") (pin "5") (pinfunction "GND_5") (pintype "power_in"))
      (node (ref "S1") (pin "1") (pinfunction "S_1") (pintype "passive"))
      (node (ref "S1") (pin "2") (pinfunction "S1_2") (pintype "passive"))
      (node (ref "S2") (pin "1") (pinfunction "S_1") (pintype "passive"))
      (node (ref "S2") (pin "2") (pinfunction "S1_2") (pintype "passive"))
      (node (ref "S3") (pin "1") (pinfunction "S_1") (pintype "passive"))
      (node (ref "S3") (pin "2") (pinfunction "S1_2") (pintype "passive"))
      (node (ref "S4") (pin "1") (pinfunction "S_1") (pintype "passive"))
      (node (ref "S4") (pin "2") (pinfunction "S1_2") (pintype "passive"))
      (node (ref "S5") (pin "1") (pinfunction "S_1") (pintype "passive"))
      (node (ref "S5") (pin "2") (pinfunction "S1_2") (pintype "passive"))
      (node (ref "S6") (pin "1") (pinfunction "S_1") (pintype "passive"))
      (node (ref "S6") (pin "2") (pinfunction "S1_2") (pintype "passive"))
      (node (ref "U$2") (pin "GND") (pinfunction "GND_GND") (pintype "bidirectional"))
      (node (ref "U$3") (pin "9") (pinfunction "VSS_9") (pintype "bidirectional"))
      (node (ref "UART_GND/TX/RX/VCC") (pin "1") (pinfunction "1_1") (pintype "passive"))
      (node (ref "VCC_CHECK") (pin "K") (pinfunction "C_K") (pintype "passive"))
      (node (ref "VCC_OUT") (pin "2") (pinfunction "1_2") (pintype "passive"))
      (node (ref "X2") (pin "4") (pinfunction "4_4") (pintype "passive"))
    )
    (net (code "28") (name "Net-(1/2/3/4/5/6-1)") (class "Default")
      (node (ref "1/2/3/4/5/6") (pin "6") (pinfunction "1_6") (pintype "passive"))
      (node (ref "R24") (pin "1") (pinfunction "1_1") (pintype "passive"))
    )
    (net (code "29") (name "Net-(1/2/3/4/5/6-2)") (class "Default")
      (node (ref "1/2/3/4/5/6") (pin "5") (pinfunction "2_5") (pintype "passive"))
      (node (ref "R13") (pin "2") (pinfunction "2_2") (pintype "passive"))
    )
    (net (code "30") (name "Net-(1/2/3/4/5/6-3)") (class "Default")
      (node (ref "1/2/3/4/5/6") (pin "4") (pinfunction "3_4") (pintype "passive"))
      (node (ref "R14") (pin "2") (pinfunction "2_2") (pintype "passive"))
    )
    (net (code "31") (name "Net-(1/2/3/4/5/6-4)") (class "Default")
      (node (ref "1/2/3/4/5/6") (pin "3") (pinfunction "4_3") (pintype "passive"))
      (node (ref "R15") (pin "2") (pinfunction "2_2") (pintype "passive"))
    )
    (net (code "32") (name "Net-(1/2/3/4/5/6-5)") (class "Default")
      (node (ref "1/2/3/4/5/6") (pin "2") (pinfunction "5_2") (pintype "passive"))
      (node (ref "R16") (pin "2") (pinfunction "2_2") (pintype "passive"))
    )
    (net (code "33") (name "Net-(1/2/3/4/5/6-6)") (class "Default")
      (node (ref "1/2/3/4/5/6") (pin "1") (pinfunction "6_1") (pintype "passive"))
      (node (ref "R17") (pin "2") (pinfunction "2_2") (pintype "passive"))
    )
    (net (code "34") (name "Net-(12/11/10/9/8/7-1)") (class "Default")
      (node (ref "12/11/10/9/8/7") (pin "6") (pinfunction "1_6") (pintype "passive"))
      (node (ref "R20") (pin "1") (pinfunction "1_1") (pintype "passive"))
    )
    (net (code "35") (name "Net-(12/11/10/9/8/7-2)") (class "Default")
      (node (ref "12/11/10/9/8/7") (pin "5") (pinfunction "2_5") (pintype "passive"))
      (node (ref "R27") (pin "2") (pinfunction "2_2") (pintype "passive"))
    )
    (net (code "36") (name "Net-(12/11/10/9/8/7-3)") (class "Default")
      (node (ref "12/11/10/9/8/7") (pin "4") (pinfunction "3_4") (pintype "passive"))
      (node (ref "R19") (pin "2") (pinfunction "2_2") (pintype "passive"))
    )
    (net (code "37") (name "Net-(12/11/10/9/8/7-4)") (class "Default")
      (node (ref "12/11/10/9/8/7") (pin "3") (pinfunction "4_3") (pintype "passive"))
      (node (ref "R26") (pin "1") (pinfunction "1_1") (pintype "passive"))
    )
    (net (code "38") (name "Net-(12/11/10/9/8/7-5)") (class "Default")
      (node (ref "12/11/10/9/8/7") (pin "2") (pinfunction "5_2") (pintype "passive"))
      (node (ref "R25") (pin "1") (pinfunction "1_1") (pintype "passive"))
    )
    (net (code "39") (name "Net-(12/11/10/9/8/7-6)") (class "Default")
      (node (ref "12/11/10/9/8/7") (pin "1") (pinfunction "6_1") (pintype "passive"))
      (node (ref "R18") (pin "2") (pinfunction "2_2") (pintype "passive"))
    )
    (net (code "40") (name "Net-(B/A-1)") (class "Default")
      (node (ref "B/A") (pin "2") (pinfunction "1_2") (pintype "passive"))
      (node (ref "RS-485") (pin "6") (pinfunction "A_6") (pintype "output"))
    )
    (net (code "41") (name "Net-(B/A-2)") (class "Default")
      (node (ref "B/A") (pin "1") (pinfunction "2_1") (pintype "passive"))
      (node (ref "RS-485") (pin "7") (pinfunction "B_7") (pintype "output"))
    )
    (net (code "42") (name "Net-(BUZZER-Pad1)") (class "Default")
      (node (ref "BUZZER") (pin "1") (pinfunction "1_1") (pintype "passive"))
      (node (ref "R22") (pin "2") (pinfunction "2_2") (pintype "passive"))
    )
    (net (code "43") (name "Net-(CANT_VCC-1)") (class "Default")
      (node (ref "CANT_VCC") (pin "2") (pinfunction "1_2") (pintype "passive"))
      (node (ref "MCP2551") (pin "2") (pinfunction "VSS_2") (pintype "passive"))
    )
    (net (code "44") (name "Net-(CAN_RESET_SWITCH-P)") (class "Default")
      (node (ref "C18") (pin "1") (pinfunction "1_1") (pintype "passive"))
      (node (ref "CAN_RESET") (pin "1") (pinfunction "1_1") (pintype "passive"))
      (node (ref "CAN_RESET_SWITCH") (pin "3") (pinfunction "P_3") (pintype "passive"))
      (node (ref "CAN_RESET_SWITCH") (pin "4") (pinfunction "P1_4") (pintype "passive"))
      (node (ref "R30") (pin "2") (pinfunction "2_2") (pintype "passive"))
    )
    (net (code "45") (name "Net-(CAN_VCC-1)") (class "Default")
      (node (ref "CAN_VCC") (pin "2") (pinfunction "1_2") (pintype "passive"))
      (node (ref "U$3") (pin "18") (pinfunction "VDD_18") (pintype "bidirectional"))
    )
    (net (code "46") (name "Net-(ENC-PadA)") (class "Default")
      (node (ref "ENC") (pin "A") (pinfunction "A_A") (pintype "passive"))
      (node (ref "ENCODER") (pin "1") (pinfunction "1_1") (pintype "passive"))
      (node (ref "R29") (pin "1") (pinfunction "1_1") (pintype "passive"))
    )
    (net (code "47") (name "Net-(ENC-PadB)") (class "Default")
      (node (ref "ENC") (pin "B") (pinfunction "B_B") (pintype "passive"))
      (node (ref "ENCODER") (pin "2") (pinfunction "2_2") (pintype "passive"))
      (node (ref "R28") (pin "1") (pinfunction "1_1") (pintype "passive"))
    )
    (net (code "48") (name "Net-(ENCB-2)") (class "Default")
      (node (ref "ENC") (pin "E") (pinfunction "2_E") (pintype "passive"))
      (node (ref "ENCODER") (pin "3") (pinfunction "3_3") (pintype "passive"))
      (node (ref "R23") (pin "1") (pinfunction "1_1") (pintype "passive"))
    )
    (net (code "49") (name "Net-(IC1-AVCC)") (class "Default")
      (node (ref "C11") (pin "+") (pinfunction "+_+") (pintype "passive"))
      (node (ref "C9") (pin "1") (pinfunction "1_1") (pintype "passive"))
      (node (ref "IC1") (pin "30") (pinfunction "AVCC_30") (pintype "power_in"))
      (node (ref "L2") (pin "2") (pinfunction "2_2") (pintype "passive"))
    )
    (net (code "50") (name "Net-(IC2-VI)") (class "Default")
      (node (ref "C1") (pin "+") (pinfunction "+_+") (pintype "passive"))
      (node (ref "F1") (pin "2A") (pinfunction "2A_2A") (pintype "passive"))
      (node (ref "IC2") (pin "1") (pinfunction "VI_1") (pintype "input"))
    )
    (net (code "51") (name "Net-(IC3-SCL)") (class "Default")
      (node (ref "IC3") (pin "6") (pinfunction "SCL_6") (pintype "bidirectional"))
      (node (ref "SDA/SCL/SQW_OUT/_RTC") (pin "2") (pinfunction "2_2") (pintype "passive"))
    )
    (net (code "52") (name "Net-(IC3-SDA)") (class "Default")
      (node (ref "IC3") (pin "5") (pinfunction "SDA_5") (pintype "bidirectional"))
      (node (ref "SDA/SCL/SQW_OUT/_RTC") (pin "1") (pinfunction "1_1") (pintype "passive"))
    )
    (net (code "53") (name "Net-(IC3-VBAT)") (class "Default")
      (node (ref "G1") (pin "+") (pinfunction "+_+") (pintype "passive"))
      (node (ref "IC3") (pin "3") (pinfunction "VBAT_3") (pintype "power_in"))
    )
    (net (code "54") (name "Net-(IC3-X1)") (class "Default")
      (node (ref "IC3") (pin "1") (pinfunction "X1_1") (pintype "passive"))
      (node (ref "Q2") (pin "1") (pinfunction "1_1") (pintype "passive"))
    )
    (net (code "55") (name "Net-(IC3-X2)") (class "Default")
      (node (ref "IC3") (pin "2") (pinfunction "X2_2") (pintype "passive"))
      (node (ref "Q2") (pin "2") (pinfunction "2_2") (pintype "passive"))
    )
    (net (code "56") (name "Net-(J1-Pad1)") (class "Default")
      (node (ref "J1") (pin "1") (pinfunction "1_1") (pintype "passive"))
      (node (ref "VCC_IN") (pin "1") (pinfunction "1_1") (pintype "passive"))
    )
    (net (code "57") (name "Net-(LCD-DB4)") (class "Default")
      (node (ref "LCD") (pin "11") (pinfunction "DB4_11") (pintype "bidirectional"))
      (node (ref "RS/RW/E/DB4..DB7") (pin "4") (pinfunction "4_4") (pintype "passive"))
    )
    (net (code "58") (name "Net-(LCD-DB5)") (class "Default")
      (node (ref "LCD") (pin "12") (pinfunction "DB5_12") (pintype "bidirectional"))
      (node (ref "RS/RW/E/DB4..DB7") (pin "3") (pinfunction "3_3") (pintype "passive"))
    )
    (net (code "59") (name "Net-(LCD-DB6)") (class "Default")
      (node (ref "LCD") (pin "13") (pinfunction "DB6_13") (pintype "bidirectional"))
      (node (ref "RS/RW/E/DB4..DB7") (pin "2") (pinfunction "2_2") (pintype "passive"))
    )
    (net (code "60") (name "Net-(LCD-DB7)") (class "Default")
      (node (ref "LCD") (pin "14") (pinfunction "DB7_14") (pintype "bidirectional"))
      (node (ref "RS/RW/E/DB4..DB7") (pin "1") (pinfunction "1_1") (pintype "passive"))
    )
    (net (code "61") (name "Net-(LCD-E)") (class "Default")
      (node (ref "LCD") (pin "6") (pinfunction "E_6") (pintype "input"))
      (node (ref "RS/RW/E/DB4..DB7") (pin "5") (pinfunction "5_5") (pintype "passive"))
    )
    (net (code "62") (name "Net-(LCD-LEDA)") (class "Default")
      (node (ref "LCD") (pin "15") (pinfunction "LEDA_15") (pintype "passive"))
      (node (ref "LCD") (pin "2") (pinfunction "VCC_2") (pintype "power_in"))
      (node (ref "R1") (pin "A") (pinfunction "A_A") (pintype "passive"))
      (node (ref "VCC_LCD") (pin "1") (pinfunction "2_1") (pintype "passive"))
    )
    (net (code "63") (name "Net-(LCD-RS)") (class "Default")
      (node (ref "LCD") (pin "4") (pinfunction "RS_4") (pintype "input"))
      (node (ref "RS/RW/E/DB4..DB7") (pin "7") (pinfunction "7_7") (pintype "passive"))
    )
    (net (code "64") (name "Net-(LCD-R{slash}W)") (class "Default")
      (node (ref "LCD") (pin "5") (pinfunction "R/W_5") (pintype "input"))
      (node (ref "RS/RW/E/DB4..DB7") (pin "6") (pinfunction "6_6") (pintype "passive"))
    )
    (net (code "65") (name "Net-(LCD-VO)") (class "Default")
      (node (ref "LCD") (pin "3") (pinfunction "VO_3") (pintype "input"))
      (node (ref "R1") (pin "S") (pinfunction "S_S") (pintype "passive"))
    )
    (net (code "66") (name "Net-(LED1-C)") (class "Default")
      (node (ref "LED1") (pin "K") (pinfunction "C_K") (pintype "passive"))
      (node (ref "R3") (pin "1") (pinfunction "1_1") (pintype "passive"))
    )
    (net (code "67") (name "Net-(LED1/LED2-1)") (class "Default")
      (node (ref "LED1") (pin "A") (pinfunction "A_A") (pintype "passive"))
      (node (ref "LED1/LED2") (pin "2") (pinfunction "1_2") (pintype "passive"))
    )
    (net (code "68") (name "Net-(LED1/LED2-2)") (class "Default")
      (node (ref "LED1/LED2") (pin "1") (pinfunction "2_1") (pintype "passive"))
      (node (ref "LED2") (pin "A") (pinfunction "A_A") (pintype "passive"))
    )
    (net (code "69") (name "Net-(LED2-C)") (class "Default")
      (node (ref "LED2") (pin "K") (pinfunction "C_K") (pintype "passive"))
      (node (ref "R4") (pin "1") (pinfunction "1_1") (pintype "passive"))
    )
    (net (code "70") (name "Net-(LED3-C)") (class "Default")
      (node (ref "LED3") (pin "K") (pinfunction "C_K") (pintype "passive"))
      (node (ref "R5") (pin "1") (pinfunction "1_1") (pintype "passive"))
    )
    (net (code "71") (name "Net-(LED3/LED4-1)") (class "Default")
      (node (ref "LED3") (pin "A") (pinfunction "A_A") (pintype "passive"))
      (node (ref "LED3/LED4") (pin "2") (pinfunction "1_2") (pintype "passive"))
    )
    (net (code "72") (name "Net-(LED3/LED4-2)") (class "Default")
      (node (ref "LED3/LED4") (pin "1") (pinfunction "2_1") (pintype "passive"))
      (node (ref "LED4") (pin "A") (pinfunction "A_A") (pintype "passive"))
    )
    (net (code "73") (name "Net-(LED4-C)") (class "Default")
      (node (ref "LED4") (pin "K") (pinfunction "C_K") (pintype "passive"))
      (node (ref "R6") (pin "1") (pinfunction "1_1") (pintype "passive"))
    )
    (net (code "74") (name "Net-(LED5-C)") (class "Default")
      (node (ref "LED5") (pin "K") (pinfunction "C_K") (pintype "passive"))
      (node (ref "R9") (pin "1") (pinfunction "1_1") (pintype "passive"))
    )
    (net (code "75") (name "Net-(LED5/LED6-1)") (class "Default")
      (node (ref "LED5") (pin "A") (pinfunction "A_A") (pintype "passive"))
      (node (ref "LED5/LED6") (pin "2") (pinfunction "1_2") (pintype "passive"))
    )
    (net (code "76") (name "Net-(LED5/LED6-2)") (class "Default")
      (node (ref "LED5/LED6") (pin "1") (pinfunction "2_1") (pintype "passive"))
      (node (ref "LED6") (pin "A") (pinfunction "A_A") (pintype "passive"))
    )
    (net (code "77") (name "Net-(LED6-C)") (class "Default")
      (node (ref "LED6") (pin "K") (pinfunction "C_K") (pintype "passive"))
      (node (ref "R10") (pin "1") (pinfunction "1_1") (pintype "passive"))
    )
    (net (code "78") (name "Net-(LED7-C)") (class "Default")
      (node (ref "LED7") (pin "K") (pinfunction "C_K") (pintype "passive"))
      (node (ref "R11") (pin "1") (pinfunction "1_1") (pintype "passive"))
    )
    (net (code "79") (name "Net-(LED7/LED8-1)") (class "Default")
      (node (ref "LED7") (pin "A") (pinfunction "A_A") (pintype "passive"))
      (node (ref "LED7/LED8") (pin "2") (pinfunction "1_2") (pintype "passive"))
    )
    (net (code "80") (name "Net-(LED7/LED8-2)") (class "Default")
      (node (ref "LED7/LED8") (pin "1") (pinfunction "2_1") (pintype "passive"))
      (node (ref "LED8") (pin "A") (pinfunction "A_A") (pintype "passive"))
    )
    (net (code "81") (name "Net-(LED8-C)") (class "Default")
      (node (ref "LED8") (pin "K") (pinfunction "C_K") (pintype "passive"))
      (node (ref "R12") (pin "1") (pinfunction "1_1") (pintype "passive"))
    )
    (net (code "82") (name "Net-(MCP2551-CANH)") (class "Default")
      (node (ref "MCP2551") (pin "7") (pinfunction "CANH_7") (pintype "passive"))
      (node (ref "RS/CH/CL/VREF") (pin "2") (pinfunction "2_2") (pintype "passive"))
    )
    (net (code "83") (name "Net-(MCP2551-CANL)") (class "Default")
      (node (ref "MCP2551") (pin "6") (pinfunction "CANL_6") (pintype "passive"))
      (node (ref "RS/CH/CL/VREF") (pin "3") (pinfunction "3_3") (pintype "passive"))
    )
    (net (code "84") (name "Net-(MCP2551-RS)") (class "Default")
      (node (ref "MCP2551") (pin "8") (pinfunction "RS_8") (pintype "passive"))
      (node (ref "RS/CH/CL/VREF") (pin "1") (pinfunction "1_1") (pintype "passive"))
    )
    (net (code "85") (name "Net-(MCP2551-VREF)") (class "Default")
      (node (ref "MCP2551") (pin "5") (pinfunction "VREF_5") (pintype "passive"))
      (node (ref "RS/CH/CL/VREF") (pin "4") (pinfunction "4_4") (pintype "passive"))
    )
    (net (code "86") (name "Net-(R2-Pad2)") (class "Default")
      (node (ref "R2") (pin "2") (pinfunction "2_2") (pintype "passive"))
      (node (ref "VCC_CHECK") (pin "A") (pinfunction "A_A") (pintype "passive"))
    )
    (net (code "87") (name "Net-(R13-Pad1)") (class "Default")
      (node (ref "R13") (pin "1") (pinfunction "1_1") (pintype "passive"))
      (node (ref "U$1") (pin "PIN5") (pinfunction "PIN5_PIN5") (pintype "bidirectional"))
    )
    (net (code "88") (name "Net-(R14-Pad1)") (class "Default")
      (node (ref "R14") (pin "1") (pinfunction "1_1") (pintype "passive"))
      (node (ref "U$1") (pin "PIN4") (pinfunction "PIN4_PIN4") (pintype "bidirectional"))
    )
    (net (code "89") (name "Net-(R15-Pad1)") (class "Default")
      (node (ref "R15") (pin "1") (pinfunction "1_1") (pintype "passive"))
      (node (ref "U$1") (pin "PIN3") (pinfunction "PIN3_PIN3") (pintype "bidirectional"))
    )
    (net (code "90") (name "Net-(R16-Pad1)") (class "Default")
      (node (ref "R16") (pin "1") (pinfunction "1_1") (pintype "passive"))
      (node (ref "U$1") (pin "PIN2") (pinfunction "PIN2_PIN2") (pintype "bidirectional"))
    )
    (net (code "91") (name "Net-(R17-Pad1)") (class "Default")
      (node (ref "R17") (pin "1") (pinfunction "1_1") (pintype "passive"))
      (node (ref "U$1") (pin "PIN1") (pinfunction "PIN1_PIN1") (pintype "bidirectional"))
    )
    (net (code "92") (name "Net-(R18-Pad1)") (class "Default")
      (node (ref "R18") (pin "1") (pinfunction "1_1") (pintype "passive"))
      (node (ref "U$1") (pin "PIN7") (pinfunction "PIN7_PIN7") (pintype "bidirectional"))
    )
    (net (code "93") (name "Net-(R19-Pad1)") (class "Default")
      (node (ref "R19") (pin "1") (pinfunction "1_1") (pintype "passive"))
      (node (ref "U$1") (pin "PIN10") (pinfunction "PIN10_PIN10") (pintype "bidirectional"))
    )
    (net (code "94") (name "Net-(R27-Pad1)") (class "Default")
      (node (ref "R27") (pin "1") (pinfunction "1_1") (pintype "passive"))
      (node (ref "U$1") (pin "PIN11") (pinfunction "PIN11_PIN11") (pintype "bidirectional"))
    )
    (net (code "95") (name "Net-(RES/CS/SO/SI/SCK/INT/RX0BF/RX1BF-1)") (class "Default")
      (node (ref "RES/CS/SO/SI/SCK/INT/RX0BF/RX1BF") (pin "8") (pinfunction "1_8") (pintype "passive"))
      (node (ref "U$3") (pin "17") (pinfunction "CAN_RESET_17") (pintype "bidirectional"))
    )
    (net (code "96") (name "Net-(RES/CS/SO/SI/SCK/INT/RX0BF/RX1BF-2)") (class "Default")
      (node (ref "RES/CS/SO/SI/SCK/INT/RX0BF/RX1BF") (pin "7") (pinfunction "2_7") (pintype "passive"))
      (node (ref "U$3") (pin "16") (pinfunction "CS_16") (pintype "bidirectional"))
    )
    (net (code "97") (name "Net-(RES/CS/SO/SI/SCK/INT/RX0BF/RX1BF-3)") (class "Default")
      (node (ref "RES/CS/SO/SI/SCK/INT/RX0BF/RX1BF") (pin "6") (pinfunction "3_6") (pintype "passive"))
      (node (ref "U$3") (pin "15") (pinfunction "SO_15") (pintype "bidirectional"))
    )
    (net (code "98") (name "Net-(RES/CS/SO/SI/SCK/INT/RX0BF/RX1BF-4)") (class "Default")
      (node (ref "RES/CS/SO/SI/SCK/INT/RX0BF/RX1BF") (pin "5") (pinfunction "4_5") (pintype "passive"))
      (node (ref "U$3") (pin "14") (pinfunction "SI_14") (pintype "bidirectional"))
    )
    (net (code "99") (name "Net-(RES/CS/SO/SI/SCK/INT/RX0BF/RX1BF-5)") (class "Default")
      (node (ref "RES/CS/SO/SI/SCK/INT/RX0BF/RX1BF") (pin "4") (pinfunction "5_4") (pintype "passive"))
      (node (ref "U$3") (pin "13") (pinfunction "SCK_13") (pintype "bidirectional"))
    )
    (net (code "100") (name "Net-(RES/CS/SO/SI/SCK/INT/RX0BF/RX1BF-6)") (class "Default")
      (node (ref "RES/CS/SO/SI/SCK/INT/RX0BF/RX1BF") (pin "3") (pinfunction "6_3") (pintype "passive"))
      (node (ref "U$3") (pin "12") (pinfunction "INT_12") (pintype "bidirectional"))
    )
    (net (code "101") (name "Net-(RES/CS/SO/SI/SCK/INT/RX0BF/RX1BF-7)") (class "Default")
      (node (ref "RES/CS/SO/SI/SCK/INT/RX0BF/RX1BF") (pin "2") (pinfunction "7_2") (pintype "passive"))
      (node (ref "U$3") (pin "11") (pinfunction "RX0BF_11") (pintype "bidirectional"))
    )
    (net (code "102") (name "Net-(RES/CS/SO/SI/SCK/INT/RX0BF/RX1BF-8)") (class "Default")
      (node (ref "RES/CS/SO/SI/SCK/INT/RX0BF/RX1BF") (pin "1") (pinfunction "8_1") (pintype "passive"))
      (node (ref "U$3") (pin "10") (pinfunction "RX1BF_10") (pintype "bidirectional"))
    )
    (net (code "103") (name "Net-(RS-485-D)") (class "Default")
      (node (ref "RO/RE/DE/DI") (pin "4") (pinfunction "4_4") (pintype "passive"))
      (node (ref "RS-485") (pin "4") (pinfunction "D_4") (pintype "input"))
    )
    (net (code "104") (name "Net-(RS-485-DE)") (class "Default")
      (node (ref "RO/RE/DE/DI") (pin "3") (pinfunction "3_3") (pintype "passive"))
      (node (ref "RS-485") (pin "3") (pinfunction "DE_3") (pintype "input"))
    )
    (net (code "105") (name "Net-(RS-485-R)") (class "Default")
      (node (ref "RO/RE/DE/DI") (pin "1") (pinfunction "1_1") (pintype "passive"))
      (node (ref "RS-485") (pin "1") (pinfunction "R_1") (pintype "input"))
    )
    (net (code "106") (name "Net-(RS-485-VCC)") (class "Default")
      (node (ref "RS-485") (pin "8") (pinfunction "VCC_8") (pintype "power_in"))
      (node (ref "RS-485_VCC") (pin "2") (pinfunction "1_2") (pintype "passive"))
    )
    (net (code "107") (name "Net-(RS-485-~{RE})") (class "Default")
      (node (ref "RO/RE/DE/DI") (pin "2") (pinfunction "2_2") (pintype "passive"))
      (node (ref "RS-485") (pin "2") (pinfunction "~{RE}_2") (pintype "input"))
    )
    (net (code "108") (name "Net-(S1-P)") (class "Default")
      (node (ref "C12") (pin "1") (pinfunction "1_1") (pintype "passive"))
      (node (ref "S1") (pin "3") (pinfunction "P_3") (pintype "passive"))
      (node (ref "S1") (pin "4") (pinfunction "P1_4") (pintype "passive"))
      (node (ref "SW1_SW2") (pin "2") (pinfunction "1_2") (pintype "passive"))
    )
    (net (code "109") (name "Net-(S2-P)") (class "Default")
      (node (ref "C13") (pin "1") (pinfunction "1_1") (pintype "passive"))
      (node (ref "S2") (pin "3") (pinfunction "P_3") (pintype "passive"))
      (node (ref "S2") (pin "4") (pinfunction "P1_4") (pintype "passive"))
      (node (ref "SW1_SW2") (pin "1") (pinfunction "2_1") (pintype "passive"))
    )
    (net (code "110") (name "Net-(S3-P)") (class "Default")
      (node (ref "C14") (pin "1") (pinfunction "1_1") (pintype "passive"))
      (node (ref "S3") (pin "3") (pinfunction "P_3") (pintype "passive"))
      (node (ref "S3") (pin "4") (pinfunction "P1_4") (pintype "passive"))
      (node (ref "SW3_SW4") (pin "2") (pinfunction "1_2") (pintype "passive"))
    )
    (net (code "111") (name "Net-(S4-P)") (class "Default")
      (node (ref "C15") (pin "1") (pinfunction "1_1") (pintype "passive"))
      (node (ref "S4") (pin "3") (pinfunction "P_3") (pintype "passive"))
      (node (ref "S4") (pin "4") (pinfunction "P1_4") (pintype "passive"))
      (node (ref "SW3_SW4") (pin "1") (pinfunction "2_1") (pintype "passive"))
    )
    (net (code "112") (name "Net-(S5-P)") (class "Default")
      (node (ref "C16") (pin "1") (pinfunction "1_1") (pintype "passive"))
      (node (ref "S5") (pin "3") (pinfunction "P_3") (pintype "passive"))
      (node (ref "S5") (pin "4") (pinfunction "P1_4") (pintype "passive"))
      (node (ref "SW5_SW6") (pin "2") (pinfunction "1_2") (pintype "passive"))
    )
    (net (code "113") (name "Net-(S6-P)") (class "Default")
      (node (ref "C17") (pin "1") (pinfunction "1_1") (pintype "passive"))
      (node (ref "S6") (pin "3") (pinfunction "P_3") (pintype "passive"))
      (node (ref "S6") (pin "4") (pinfunction "P1_4") (pintype "passive"))
      (node (ref "SW5_SW6") (pin "1") (pinfunction "2_1") (pintype "passive"))
    )
    (net (code "114") (name "Net-(T1-B)") (class "Default")
      (node (ref "R24") (pin "2") (pinfunction "2_2") (pintype "passive"))
      (node (ref "T1") (pin "2") (pinfunction "B_2") (pintype "passive"))
    )
    (net (code "115") (name "Net-(T1-E)") (class "Default")
      (node (ref "T1") (pin "1") (pinfunction "E_1") (pintype "passive"))
      (node (ref "U$1") (pin "PIN6") (pinfunction "PIN6_PIN6") (pintype "bidirectional"))
    )
    (net (code "116") (name "Net-(T2-B)") (class "Default")
      (node (ref "R25") (pin "2") (pinfunction "2_2") (pintype "passive"))
      (node (ref "T2") (pin "2") (pinfunction "B_2") (pintype "passive"))
    )
    (net (code "117") (name "Net-(T2-E)") (class "Default")
      (node (ref "T2") (pin "1") (pinfunction "E_1") (pintype "passive"))
      (node (ref "U$1") (pin "PIN8") (pinfunction "PIN8_PIN8") (pintype "bidirectional"))
    )
    (net (code "118") (name "Net-(T3-B)") (class "Default")
      (node (ref "R20") (pin "2") (pinfunction "2_2") (pintype "passive"))
      (node (ref "T3") (pin "2") (pinfunction "B_2") (pintype "passive"))
    )
    (net (code "119") (name "Net-(T3-E)") (class "Default")
      (node (ref "T3") (pin "1") (pinfunction "E_1") (pintype "passive"))
      (node (ref "U$1") (pin "PIN12") (pinfunction "PIN12_PIN12") (pintype "bidirectional"))
    )
    (net (code "120") (name "Net-(T4-B)") (class "Default")
      (node (ref "R26") (pin "2") (pinfunction "2_2") (pintype "passive"))
      (node (ref "T4") (pin "2") (pinfunction "B_2") (pintype "passive"))
    )
    (net (code "121") (name "Net-(T4-E)") (class "Default")
      (node (ref "T4") (pin "1") (pinfunction "E_1") (pintype "passive"))
      (node (ref "U$1") (pin "PIN9") (pinfunction "PIN9_PIN9") (pintype "bidirectional"))
    )
    (net (code "122") (name "Net-(T5-B)") (class "Default")
      (node (ref "R22") (pin "1") (pinfunction "1_1") (pintype "passive"))
      (node (ref "T5") (pin "2") (pinfunction "B_2") (pintype "passive"))
    )
    (net (code "123") (name "Net-(T5-C)") (class "Default")
      (node (ref "R21") (pin "1") (pinfunction "1_1") (pintype "passive"))
      (node (ref "T5") (pin "3") (pinfunction "C_3") (pintype "passive"))
    )
    (net (code "124") (name "Net-(T5-E)") (class "Default")
      (node (ref "T5") (pin "1") (pinfunction "E_1") (pintype "passive"))
      (node (ref "U$2") (pin "VCC") (pinfunction "VCC_VCC") (pintype "bidirectional"))
    )
    (net (code "125") (name "Net-(TXC/RXC/CLKAOU_SOF/TX0RTS/TX1RTS/TX2RTS/OSC2/OSC1-1)") (class "Default")
      (node (ref "TXC/RXC/CLKAOU_SOF/TX0RTS/TX1RTS/TX2RTS/OSC2/OSC1") (pin "8") (pinfunction "1_8") (pintype "passive"))
      (node (ref "U$3") (pin "8") (pinfunction "OSC1_8") (pintype "bidirectional"))
    )
    (net (code "126") (name "Net-(TXC/RXC/CLKAOU_SOF/TX0RTS/TX1RTS/TX2RTS/OSC2/OSC1-2)") (class "Default")
      (node (ref "TXC/RXC/CLKAOU_SOF/TX0RTS/TX1RTS/TX2RTS/OSC2/OSC1") (pin "7") (pinfunction "2_7") (pintype "passive"))
      (node (ref "U$3") (pin "7") (pinfunction "OSC2_7") (pintype "bidirectional"))
    )
    (net (code "127") (name "Net-(TXC/RXC/CLKAOU_SOF/TX0RTS/TX1RTS/TX2RTS/OSC2/OSC1-3)") (class "Default")
      (node (ref "TXC/RXC/CLKAOU_SOF/TX0RTS/TX1RTS/TX2RTS/OSC2/OSC1") (pin "6") (pinfunction "3_6") (pintype "passive"))
      (node (ref "U$3") (pin "6") (pinfunction "TX2RTS_6") (pintype "bidirectional"))
    )
    (net (code "128") (name "Net-(TXC/RXC/CLKAOU_SOF/TX0RTS/TX1RTS/TX2RTS/OSC2/OSC1-4)") (class "Default")
      (node (ref "TXC/RXC/CLKAOU_SOF/TX0RTS/TX1RTS/TX2RTS/OSC2/OSC1") (pin "5") (pinfunction "4_5") (pintype "passive"))
      (node (ref "U$3") (pin "5") (pinfunction "TX1RTS_5") (pintype "bidirectional"))
    )
    (net (code "129") (name "Net-(TXC/RXC/CLKAOU_SOF/TX0RTS/TX1RTS/TX2RTS/OSC2/OSC1-5)") (class "Default")
      (node (ref "TXC/RXC/CLKAOU_SOF/TX0RTS/TX1RTS/TX2RTS/OSC2/OSC1") (pin "4") (pinfunction "5_4") (pintype "passive"))
      (node (ref "U$3") (pin "4") (pinfunction "TX0RTS_4") (pintype "bidirectional"))
    )
    (net (code "130") (name "Net-(TXC/RXC/CLKAOU_SOF/TX0RTS/TX1RTS/TX2RTS/OSC2/OSC1-6)") (class "Default")
      (node (ref "TXC/RXC/CLKAOU_SOF/TX0RTS/TX1RTS/TX2RTS/OSC2/OSC1") (pin "3") (pinfunction "6_3") (pintype "passive"))
      (node (ref "U$3") (pin "3") (pinfunction "CLKOUT/SOF_3") (pintype "bidirectional"))
    )
    (net (code "131") (name "Net-(TXC/RXC/CLKAOU_SOF/TX0RTS/TX1RTS/TX2RTS/OSC2/OSC1-7)") (class "Default")
      (node (ref "TXC/RXC/CLKAOU_SOF/TX0RTS/TX1RTS/TX2RTS/OSC2/OSC1") (pin "2") (pinfunction "7_2") (pintype "passive"))
      (node (ref "U$3") (pin "2") (pinfunction "RXCAN_2") (pintype "bidirectional"))
    )
    (net (code "132") (name "Net-(TXC/RXC/CLKAOU_SOF/TX0RTS/TX1RTS/TX2RTS/OSC2/OSC1-8)") (class "Default")
      (node (ref "TXC/RXC/CLKAOU_SOF/TX0RTS/TX1RTS/TX2RTS/OSC2/OSC1") (pin "1") (pinfunction "8_1") (pintype "passive"))
      (node (ref "U$3") (pin "1") (pinfunction "TXCAN_1") (pintype "bidirectional"))
    )
    (net (code "133") (name "Net-(UART_VCC-2)") (class "Default")
      (node (ref "UART_GND/TX/RX/VCC") (pin "4") (pinfunction "4_4") (pintype "passive"))
      (node (ref "UART_VCC") (pin "1") (pinfunction "2_1") (pintype "passive"))
    )
    (net (code "134") (name "Net-(VCC_IN-Pad4)") (class "Default")
      (node (ref "VCC_IN") (pin "4") (pinfunction "4_4") (pintype "passive"))
      (node (ref "X2") (pin "1") (pinfunction "1_1") (pintype "passive"))
    )
    (net (code "135") (name "Net-(VCC_KANDA-1)") (class "Default")
      (node (ref "KANDA") (pin "2") (pinfunction "2_2") (pintype "passive"))
      (node (ref "VCC_KANDA") (pin "2") (pinfunction "1_2") (pintype "passive"))
    )
    (net (code "136") (name "PINB4") (class "Default")
      (node (ref "IC1") (pin "5") (pinfunction "(SS)PB4_5") (pintype "bidirectional"))
      (node (ref "LISTWA_PINOW_1") (pin "5") (pinfunction "5_5") (pintype "passive"))
      (node (ref "SPI_SCK/MISO/MOSI/SS") (pin "1") (pinfunction "1_1") (pintype "passive"))
    )
    (net (code "137") (name "PINB5") (class "Default")
      (node (ref "IC1") (pin "6") (pinfunction "(MOSI)PB5_6") (pintype "bidirectional"))
      (node (ref "KANDA") (pin "1") (pinfunction "1_1") (pintype "passive"))
      (node (ref "LISTWA_PINOW_1") (pin "6") (pinfunction "6_6") (pintype "passive"))
      (node (ref "SPI_SCK/MISO/MOSI/SS") (pin "2") (pinfunction "2_2") (pintype "passive"))
    )
    (net (code "138") (name "PINB6") (class "Default")
      (node (ref "IC1") (pin "7") (pinfunction "(MISO)PB6_7") (pintype "bidirectional"))
      (node (ref "KANDA") (pin "9") (pinfunction "9_9") (pintype "passive"))
      (node (ref "LISTWA_PINOW_1") (pin "7") (pinfunction "7_7") (pintype "passive"))
      (node (ref "SPI_SCK/MISO/MOSI/SS") (pin "3") (pinfunction "3_3") (pintype "passive"))
    )
    (net (code "139") (name "PINB7") (class "Default")
      (node (ref "IC1") (pin "8") (pinfunction "(SCK)PB7_8") (pintype "bidirectional"))
      (node (ref "KANDA") (pin "7") (pinfunction "7_7") (pintype "passive"))
      (node (ref "LISTWA_PINOW_1") (pin "8") (pinfunction "8_8") (pintype "passive"))
      (node (ref "SPI_SCK/MISO/MOSI/SS") (pin "4") (pinfunction "4_4") (pintype "passive"))
    )
    (net (code "140") (name "PIND0") (class "Default")
      (node (ref "IC1") (pin "14") (pinfunction "(RXD)PD0_14") (pintype "bidirectional"))
      (node (ref "LISTWA_PINOW_1") (pin "9") (pinfunction "9_9") (pintype "passive"))
      (node (ref "UART_GND/TX/RX/VCC") (pin "3") (pinfunction "3_3") (pintype "passive"))
    )
    (net (code "141") (name "PIND1") (class "Default")
      (node (ref "IC1") (pin "15") (pinfunction "(TXD)PD1_15") (pintype "bidirectional"))
      (node (ref "LISTWA_PINOW_1") (pin "10") (pinfunction "10_10") (pintype "passive"))
      (node (ref "UART_GND/TX/RX/VCC") (pin "2") (pinfunction "2_2") (pintype "passive"))
    )
    (net (code "142") (name "PINDC1") (class "Default")
      (node (ref "I2C_SCL/SDA") (pin "2") (pinfunction "1_2") (pintype "passive"))
      (node (ref "IC1") (pin "22") (pinfunction "(SCL)PC0_22") (pintype "bidirectional"))
      (node (ref "LISTWA_PINOW_R_DN") (pin "8") (pinfunction "8_8") (pintype "passive"))
    )
    (net (code "143") (name "PINDC2") (class "Default")
      (node (ref "I2C_SCL/SDA") (pin "1") (pinfunction "2_1") (pintype "passive"))
      (node (ref "IC1") (pin "23") (pinfunction "(SDA)PC1_23") (pintype "bidirectional"))
      (node (ref "LISTWA_PINOW_R_DN") (pin "7") (pinfunction "7_7") (pintype "passive"))
    )
    (net (code "144") (name "RESET") (class "Default")
      (node (ref "C4") (pin "1") (pinfunction "1_1") (pintype "passive"))
      (node (ref "IC1") (pin "9") (pinfunction "RESET_9") (pintype "input"))
      (node (ref "KANDA") (pin "5") (pinfunction "5_5") (pintype "passive"))
      (node (ref "R7") (pin "2") (pinfunction "2_2") (pintype "passive"))
      (node (ref "RESET_SWITCH") (pin "3") (pinfunction "P_3") (pintype "passive"))
      (node (ref "RESET_SWITCH") (pin "4") (pinfunction "P1_4") (pintype "passive"))
    )
    (net (code "145") (name "RXD") (class "Default")
      (node (ref "MCP2551") (pin "4") (pinfunction "RXD_4") (pintype "passive"))
      (node (ref "TXD/RXD") (pin "2") (pinfunction "1_2") (pintype "passive"))
    )
    (net (code "146") (name "SQW{slash}OUT") (class "Default")
      (node (ref "IC3") (pin "7") (pinfunction "SQW/OUT_7") (pintype "bidirectional"))
      (node (ref "SDA/SCL/SQW_OUT/_RTC") (pin "3") (pinfunction "3_3") (pintype "passive"))
    )
    (net (code "147") (name "TXD") (class "Default")
      (node (ref "MCP2551") (pin "1") (pinfunction "TXD_1") (pintype "passive"))
      (node (ref "TXD/RXD") (pin "1") (pinfunction "2_1") (pintype "passive"))
    )
    (net (code "148") (name "VCC") (class "Default")
      (node (ref "C2") (pin "+") (pinfunction "+_+") (pintype "passive"))
      (node (ref "C3") (pin "1") (pinfunction "1_1") (pintype "passive"))
      (node (ref "C5") (pin "+") (pinfunction "+_+") (pintype "passive"))
      (node (ref "C6") (pin "1") (pinfunction "1_1") (pintype "passive"))
      (node (ref "CANT_VCC") (pin "1") (pinfunction "2_1") (pintype "passive"))
      (node (ref "CAN_VCC") (pin "1") (pinfunction "2_1") (pintype "passive"))
      (node (ref "IC1") (pin "10") (pinfunction "VCC_10") (pintype "power_in"))
      (node (ref "IC2") (pin "3") (pinfunction "VO_3") (pintype "passive"))
      (node (ref "IC3") (pin "8") (pinfunction "VCC_8") (pintype "power_in"))
      (node (ref "L2") (pin "1") (pinfunction "1_1") (pintype "passive"))
      (node (ref "R2") (pin "1") (pinfunction "1_1") (pintype "passive"))
      (node (ref "R21") (pin "2") (pinfunction "2_2") (pintype "passive"))
      (node (ref "R23") (pin "2") (pinfunction "2_2") (pintype "passive"))
      (node (ref "R28") (pin "2") (pinfunction "2_2") (pintype "passive"))
      (node (ref "R29") (pin "2") (pinfunction "2_2") (pintype "passive"))
      (node (ref "R30") (pin "1") (pinfunction "1_1") (pintype "passive"))
      (node (ref "R7") (pin "1") (pinfunction "1_1") (pintype "passive"))
      (node (ref "RS-485_VCC") (pin "1") (pinfunction "2_1") (pintype "passive"))
      (node (ref "T1") (pin "3") (pinfunction "C_3") (pintype "passive"))
      (node (ref "T2") (pin "3") (pinfunction "C_3") (pintype "passive"))
      (node (ref "T3") (pin "3") (pinfunction "C_3") (pintype "passive"))
      (node (ref "T4") (pin "3") (pinfunction "C_3") (pintype "passive"))
      (node (ref "UART_VCC") (pin "2") (pinfunction "1_2") (pintype "passive"))
      (node (ref "VCC_IN") (pin "3") (pinfunction "3_3") (pintype "passive"))
      (node (ref "VCC_KANDA") (pin "1") (pinfunction "2_1") (pintype "passive"))
      (node (ref "VCC_LCD") (pin "2") (pinfunction "1_2") (pintype "passive"))
      (node (ref "VCC_OUT") (pin "1") (pinfunction "2_1") (pintype "passive"))
    )
    (net (code "149") (name "VIN") (class "Default")
      (node (ref "F1") (pin "1A") (pinfunction "1A_1A") (pintype "passive"))
      (node (ref "VCC_IN") (pin "2") (pinfunction "2_2") (pintype "passive"))
    )
    (net (code "150") (name "XTAL1") (class "Default")
      (node (ref "C8") (pin "2") (pinfunction "2_2") (pintype "passive"))
      (node (ref "IC1") (pin "13") (pinfunction "XTAL1_13") (pintype "bidirectional"))
      (node (ref "JP2") (pin "1") (pinfunction "1_1") (pintype "passive"))
    )
    (net (code "151") (name "XTAL2") (class "Default")
      (node (ref "C7") (pin "2") (pinfunction "2_2") (pintype "passive"))
      (node (ref "IC1") (pin "12") (pinfunction "XTAL2_12") (pintype "bidirectional"))
      (node (ref "JP1") (pin "1") (pinfunction "1_1") (pintype "passive"))
    )
    (net (code "152") (name "unconnected-(F1-Pad1B)") (class "Default")
      (node (ref "F1") (pin "1B") (pinfunction "1B_1B") (pintype "passive"))
    )
    (net (code "153") (name "unconnected-(F1-Pad2B)") (class "Default")
      (node (ref "F1") (pin "2B") (pinfunction "2B_2B") (pintype "passive"))
    )
    (net (code "154") (name "unconnected-(G1-+-Pad+@1)") (class "Default")
      (node (ref "G1") (pin "+@1") (pinfunction "+_+@1") (pintype "passive"))
    )
    (net (code "155") (name "unconnected-(KANDA-Pad3)") (class "Default")
      (node (ref "KANDA") (pin "3") (pinfunction "3_3") (pintype "passive"))
    )
    (net (code "156") (name "unconnected-(KANDA-Pad6)") (class "Default")
      (node (ref "KANDA") (pin "6") (pinfunction "6_6") (pintype "passive"))
    )
    (net (code "157") (name "unconnected-(KANDA-Pad8)") (class "Default")
      (node (ref "KANDA") (pin "8") (pinfunction "8_8") (pintype "passive"))
    )
    (net (code "158") (name "unconnected-(KANDA-Pad10)") (class "Default")
      (node (ref "KANDA") (pin "10") (pinfunction "10_10") (pintype "passive"))
    )
    (net (code "159") (name "unconnected-(LCD-DB0-Pad7)") (class "Default")
      (node (ref "LCD") (pin "7") (pinfunction "DB0_7") (pintype "bidirectional"))
    )
    (net (code "160") (name "unconnected-(LCD-DB1-Pad8)") (class "Default")
      (node (ref "LCD") (pin "8") (pinfunction "DB1_8") (pintype "bidirectional"))
    )
    (net (code "161") (name "unconnected-(LCD-DB2-Pad9)") (class "Default")
      (node (ref "LCD") (pin "9") (pinfunction "DB2_9") (pintype "bidirectional"))
    )
    (net (code "162") (name "unconnected-(LCD-DB3-Pad10)") (class "Default")
      (node (ref "LCD") (pin "10") (pinfunction "DB3_10") (pintype "bidirectional"))
    )
    (net (code "163") (name "unconnected-(X2-Pad2)") (class "Default")
      (node (ref "X2") (pin "2") (pinfunction "2_2") (pintype "passive"))
    )
    (net (code "164") (name "unconnected-(X2-Pad3)") (class "Default")
      (node (ref "X2") (pin "3") (pinfunction "3_3") (pintype "passive"))
    )
  )
)
